# PS32_lite_rev_a_public.net
KiCad netlist of a schematic drawn in Altium Designer
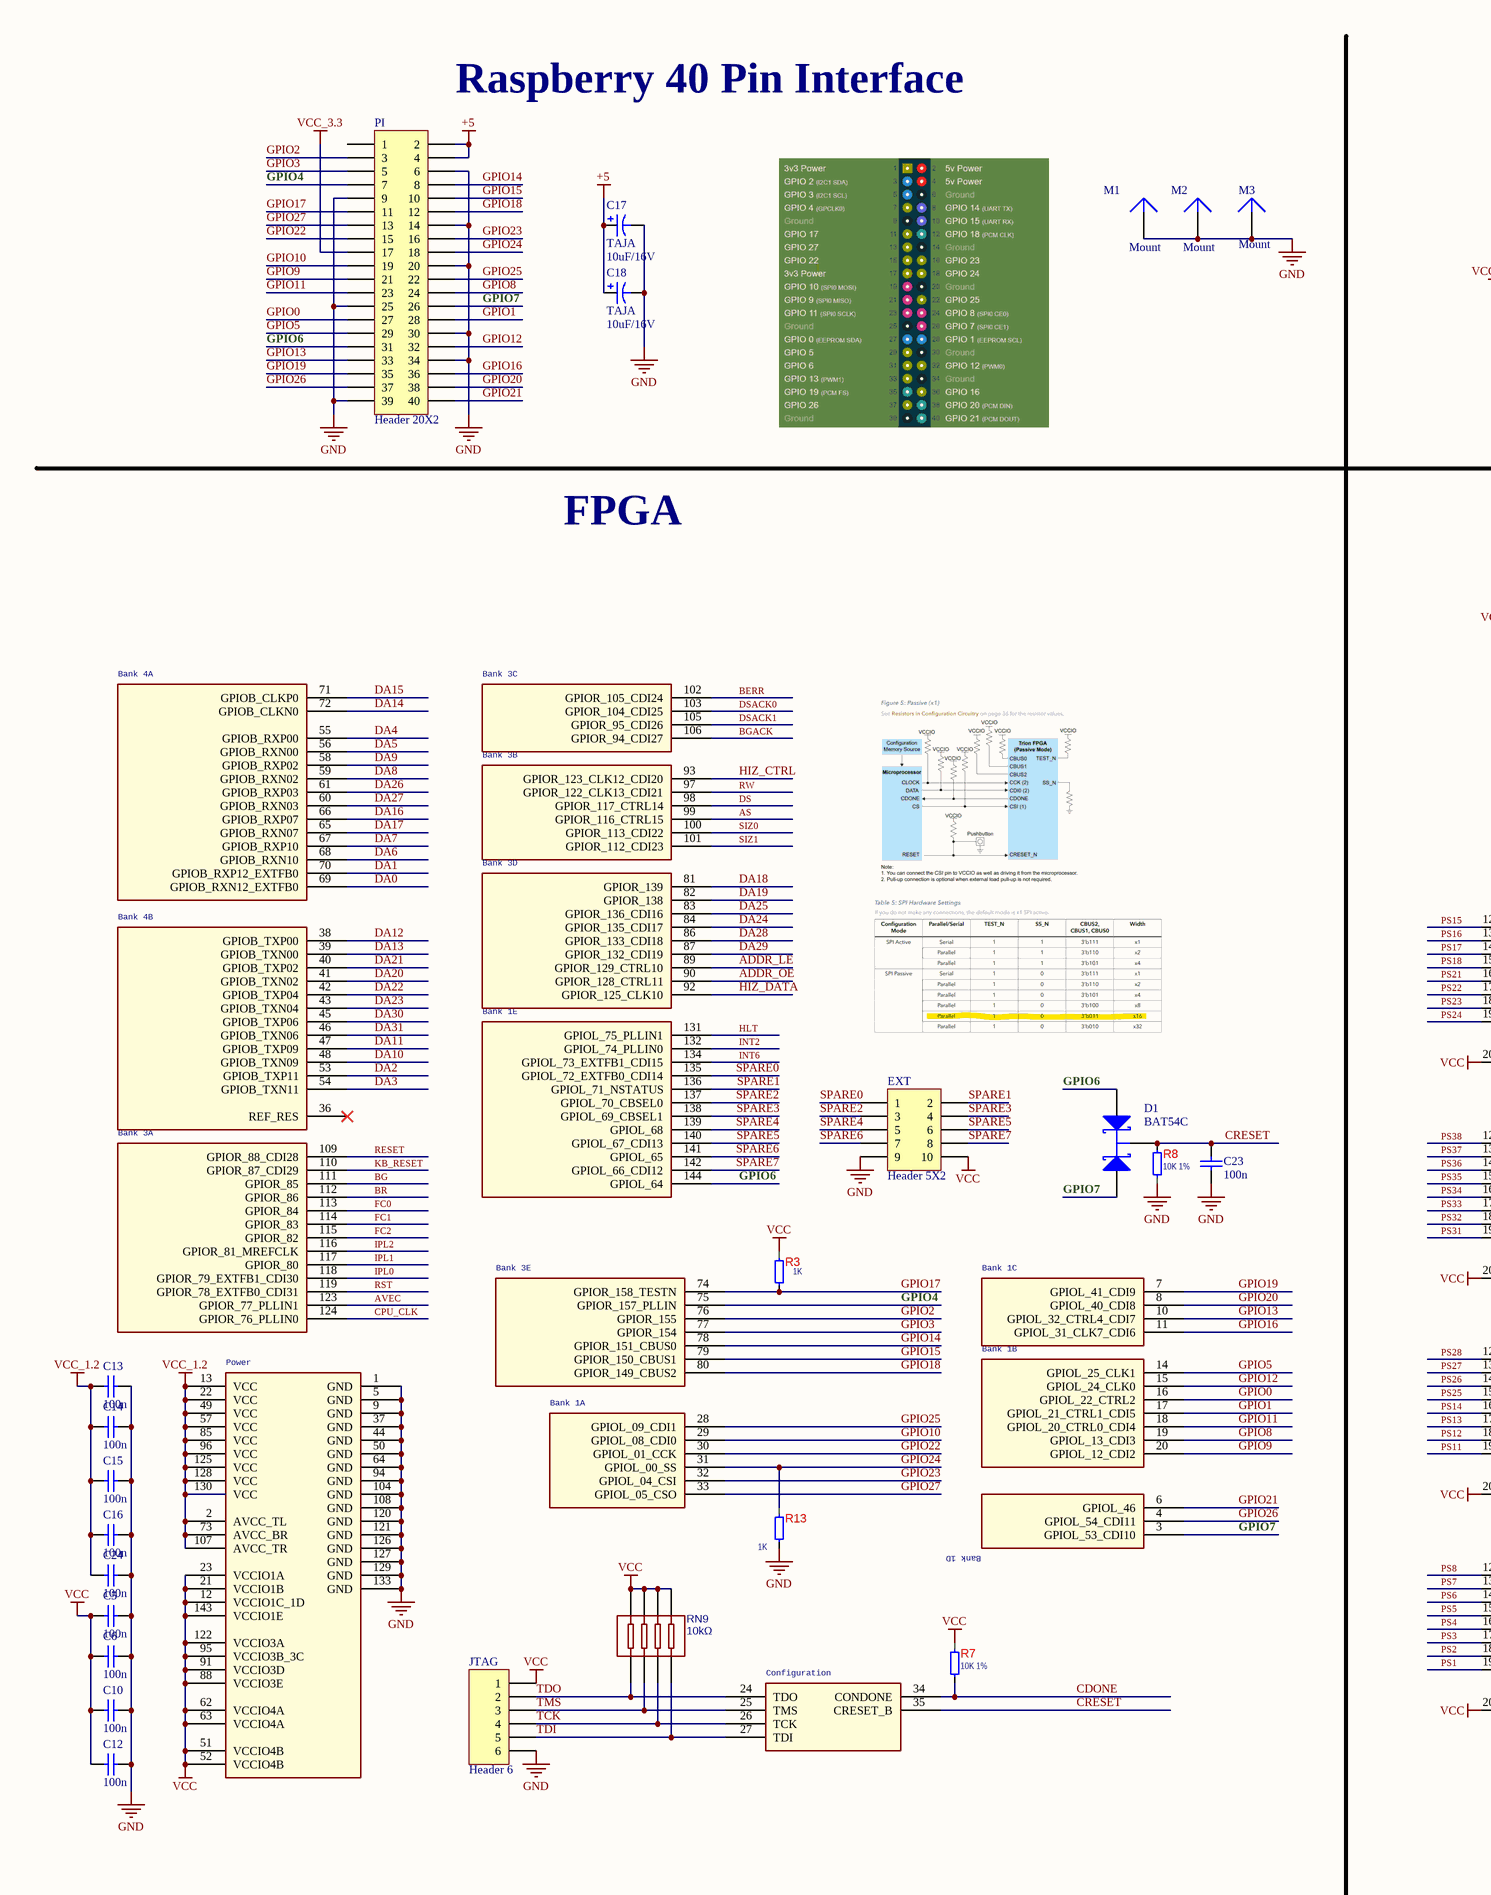
[diagram p0: PS32_lite_rev_a_public.SchDoc, left]
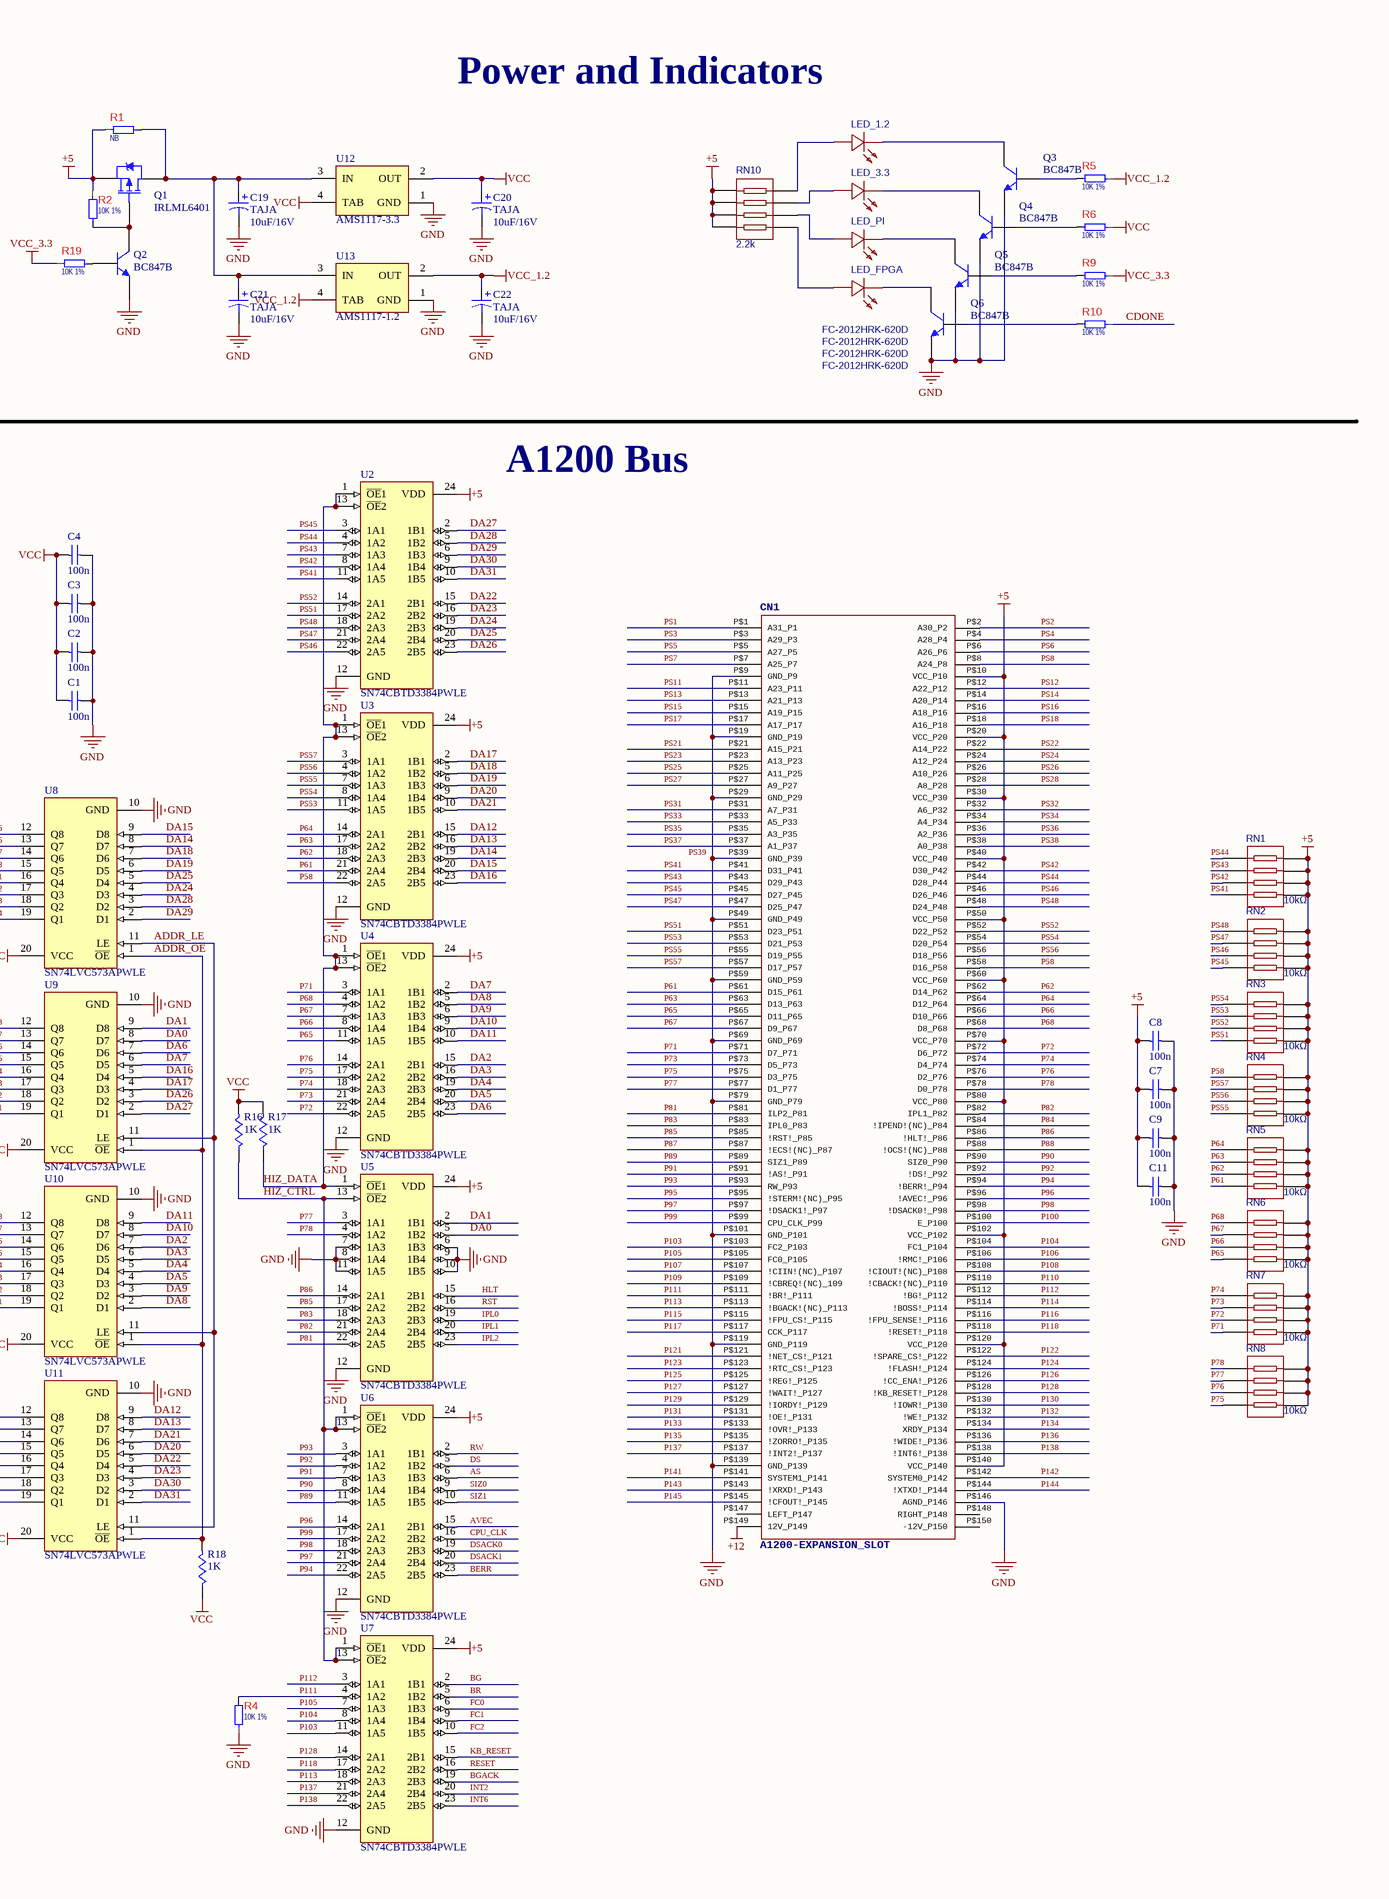
[diagram p1: PS32_lite_rev_a_public.SchDoc, right]

(export (version "E")
  (design (tool "Eeschema 10.0.6"))
  (components
    (comp (ref "C1")
      (value "100n")
      (footprint "1608[0603]")
      (description "Capacitor (Semiconductor SIM Model)")
      (fields (field (name "Comment") "Cap Semi") (field (name "PUBLISHER") "Altium Limited"))
      (libsource (lib "Miscellaneous Devices") (part "Cap Semi"))
    )
    (comp (ref "C2")
      (value "100n")
      (footprint "1608[0603]")
      (description "Capacitor (Semiconductor SIM Model)")
      (fields (field (name "Comment") "Cap Semi") (field (name "PUBLISHER") "Altium Limited"))
      (libsource (lib "Miscellaneous Devices") (part "Cap Semi"))
    )
    (comp (ref "C3")
      (value "100n")
      (footprint "1608[0603]")
      (description "Capacitor (Semiconductor SIM Model)")
      (fields (field (name "Comment") "Cap Semi") (field (name "PUBLISHER") "Altium Limited"))
      (libsource (lib "Miscellaneous Devices") (part "Cap Semi"))
    )
    (comp (ref "C4")
      (value "100n")
      (footprint "1608[0603]")
      (description "Capacitor (Semiconductor SIM Model)")
      (fields (field (name "Comment") "Cap Semi") (field (name "PUBLISHER") "Altium Limited"))
      (libsource (lib "Miscellaneous Devices") (part "Cap Semi"))
    )
    (comp (ref "C5")
      (value "100n")
      (footprint "1608[0603]")
      (description "Capacitor (Semiconductor SIM Model)")
      (fields (field (name "Comment") "Cap Semi") (field (name "PUBLISHER") "Altium Limited"))
      (libsource (lib "Miscellaneous Devices") (part "Cap Semi"))
    )
    (comp (ref "C6")
      (value "100n")
      (footprint "1608[0603]")
      (description "Capacitor (Semiconductor SIM Model)")
      (fields (field (name "Comment") "Cap Semi") (field (name "PUBLISHER") "Altium Limited"))
      (libsource (lib "Miscellaneous Devices") (part "Cap Semi"))
    )
    (comp (ref "C7")
      (value "100n")
      (footprint "1608[0603]")
      (description "Capacitor (Semiconductor SIM Model)")
      (fields (field (name "Comment") "Cap Semi") (field (name "PUBLISHER") "Altium Limited"))
      (libsource (lib "Miscellaneous Devices") (part "Cap Semi"))
    )
    (comp (ref "C8")
      (value "100n")
      (footprint "1608[0603]")
      (description "Capacitor (Semiconductor SIM Model)")
      (fields (field (name "Comment") "Cap Semi") (field (name "PUBLISHER") "Altium Limited"))
      (libsource (lib "Miscellaneous Devices") (part "Cap Semi"))
    )
    (comp (ref "C9")
      (value "100n")
      (footprint "1608[0603]")
      (description "Capacitor (Semiconductor SIM Model)")
      (fields (field (name "Comment") "Cap Semi") (field (name "PUBLISHER") "Altium Limited"))
      (libsource (lib "Miscellaneous Devices") (part "Cap Semi"))
    )
    (comp (ref "C10")
      (value "100n")
      (footprint "1608[0603]")
      (description "Capacitor (Semiconductor SIM Model)")
      (fields (field (name "Comment") "Cap Semi") (field (name "PUBLISHER") "Altium Limited"))
      (libsource (lib "Miscellaneous Devices") (part "Cap Semi"))
    )
    (comp (ref "C11")
      (value "100n")
      (footprint "1608[0603]")
      (description "Capacitor (Semiconductor SIM Model)")
      (fields (field (name "Comment") "Cap Semi") (field (name "PUBLISHER") "Altium Limited"))
      (libsource (lib "Miscellaneous Devices") (part "Cap Semi"))
    )
    (comp (ref "C12")
      (value "100n")
      (footprint "1608[0603]")
      (description "Capacitor (Semiconductor SIM Model)")
      (fields (field (name "Comment") "Cap Semi") (field (name "PUBLISHER") "Altium Limited"))
      (libsource (lib "Miscellaneous Devices") (part "Cap Semi"))
    )
    (comp (ref "C13")
      (value "100n")
      (footprint "1608[0603]")
      (description "Capacitor (Semiconductor SIM Model)")
      (fields (field (name "Comment") "Cap Semi") (field (name "PUBLISHER") "Altium Limited"))
      (libsource (lib "Miscellaneous Devices") (part "Cap Semi"))
    )
    (comp (ref "C14")
      (value "100n")
      (footprint "1608[0603]")
      (description "Capacitor (Semiconductor SIM Model)")
      (fields (field (name "Comment") "Cap Semi") (field (name "PUBLISHER") "Altium Limited"))
      (libsource (lib "Miscellaneous Devices") (part "Cap Semi"))
    )
    (comp (ref "C15")
      (value "100n")
      (footprint "1608[0603]")
      (description "Capacitor (Semiconductor SIM Model)")
      (fields (field (name "Comment") "Cap Semi") (field (name "PUBLISHER") "Altium Limited"))
      (libsource (lib "Miscellaneous Devices") (part "Cap Semi"))
    )
    (comp (ref "C16")
      (value "100n")
      (footprint "1608[0603]")
      (description "Capacitor (Semiconductor SIM Model)")
      (fields (field (name "Comment") "Cap Semi") (field (name "PUBLISHER") "Altium Limited"))
      (libsource (lib "Miscellaneous Devices") (part "Cap Semi"))
    )
    (comp (ref "C17")
      (value "TAJA")
      (footprint "T")
      (description "Solid Tantalum Chip Capacitor, Low Profile T491 Series - Industrial Grade")
      (fields (field (name "ALTIUM_VALUE") "10uF/16V") (field (name "PUBLISHER") "Altium Limited"))
      (libsource (lib "KEMET Chip Capacitor") (part "T491T"))
    )
    (comp (ref "C18")
      (value "TAJA")
      (footprint "T")
      (description "Solid Tantalum Chip Capacitor, Low Profile T491 Series - Industrial Grade")
      (fields (field (name "ALTIUM_VALUE") "10uF/16V") (field (name "PUBLISHER") "Altium Limited"))
      (libsource (lib "KEMET Chip Capacitor") (part "T491T"))
    )
    (comp (ref "C19")
      (value "TAJA")
      (footprint "T")
      (description "Solid Tantalum Chip Capacitor, Low Profile T491 Series - Industrial Grade")
      (fields (field (name "ALTIUM_VALUE") "10uF/16V") (field (name "PUBLISHER") "Altium Limited"))
      (libsource (lib "KEMET Chip Capacitor") (part "T491T"))
    )
    (comp (ref "C20")
      (value "TAJA")
      (footprint "T")
      (description "Solid Tantalum Chip Capacitor, Low Profile T491 Series - Industrial Grade")
      (fields (field (name "ALTIUM_VALUE") "10uF/16V") (field (name "PUBLISHER") "Altium Limited"))
      (libsource (lib "KEMET Chip Capacitor") (part "T491T"))
    )
    (comp (ref "C21")
      (value "TAJA")
      (footprint "T")
      (description "Solid Tantalum Chip Capacitor, Low Profile T491 Series - Industrial Grade")
      (fields (field (name "ALTIUM_VALUE") "10uF/16V") (field (name "PUBLISHER") "Altium Limited"))
      (libsource (lib "KEMET Chip Capacitor") (part "T491T"))
    )
    (comp (ref "C22")
      (value "TAJA")
      (footprint "T")
      (description "Solid Tantalum Chip Capacitor, Low Profile T491 Series - Industrial Grade")
      (fields (field (name "ALTIUM_VALUE") "10uF/16V") (field (name "PUBLISHER") "Altium Limited"))
      (libsource (lib "KEMET Chip Capacitor") (part "T491T"))
    )
    (comp (ref "C23")
      (value "100n")
      (footprint "1608[0603]")
      (description "Capacitor (Semiconductor SIM Model)")
      (fields (field (name "Comment") "Cap Semi") (field (name "PUBLISHER") "Altium Limited"))
      (libsource (lib "Miscellaneous Devices") (part "Cap Semi"))
    )
    (comp (ref "C24")
      (value "100n")
      (footprint "1608[0603]")
      (description "Capacitor (Semiconductor SIM Model)")
      (fields (field (name "Comment") "Cap Semi") (field (name "PUBLISHER") "Altium Limited"))
      (libsource (lib "Miscellaneous Devices") (part "Cap Semi"))
    )
    (comp (ref "CN1")
      (value "A1200-EXPANSION_SLOT")
      (footprint "CON_150")
      (libsource (lib "Amiga") (part "A1200-EXPANSION_SLOT-SMALL-HOLES"))
    )
    (comp (ref "D1")
      (value "BAT54C")
      (footprint "SOT23_N")
      (description "Schottky Barrier Double Diode")
      (fields (field (name "PUBLISHER") "Altium Limited"))
      (libsource (lib "Philips Discrete Diode - Schottky") (part "BAT54C"))
    )
    (comp (ref "EXT")
      (value "Header 5X2")
      (footprint "HDR2X5")
      (description "Header, 5-Pin, Dual row")
      (fields (field (name "PUBLISHER") "Altium Limited"))
      (libsource (lib "Miscellaneous Connectors") (part "Header 5X2"))
    )
    (comp (ref "JTAG")
      (value "Header 6")
      (footprint "HDR1X6")
      (description "Header, 6-Pin")
      (fields (field (name "PUBLISHER") "Altium Limited"))
      (libsource (lib "Miscellaneous Connectors") (part "Header 6"))
    )
    (comp (ref "LED_1.2")
      (value "FC-2012HRK-620D")
      (footprint "LED0805-RD")
      (fields (field (name "BOM_SUPPLIER PART") "C84256"))
      (libsource (lib "altium-import") (part "root_2_FC-2012HRK-620D_"))
    )
    (comp (ref "LED_3.3")
      (value "FC-2012HRK-620D")
      (footprint "LED0805-RD")
      (fields (field (name "BOM_SUPPLIER PART") "C84256"))
      (libsource (lib "altium-import") (part "root_2_FC-2012HRK-620D_"))
    )
    (comp (ref "LED_FPGA")
      (value "FC-2012HRK-620D")
      (footprint "LED0805-RD")
      (fields (field (name "BOM_SUPPLIER PART") "C84256"))
      (libsource (lib "altium-import") (part "root_2_FC-2012HRK-620D_"))
    )
    (comp (ref "LED_PI")
      (value "FC-2012HRK-620D")
      (footprint "LED0805-RD")
      (fields (field (name "BOM_SUPPLIER PART") "C84256"))
      (libsource (lib "altium-import") (part "root_2_FC-2012HRK-620D_"))
    )
    (comp (ref "M1")
      (value "Mount")
      (footprint "9774045151")
      (description "Plug")
      (fields (field (name "PUBLISHER") "Altium Limited"))
      (libsource (lib "Miscellaneous Connectors") (part "Plug"))
    )
    (comp (ref "M2")
      (value "Mount")
      (footprint "9774045151")
      (description "Plug")
      (fields (field (name "PUBLISHER") "Altium Limited"))
      (libsource (lib "Miscellaneous Connectors") (part "Plug"))
    )
    (comp (ref "M3")
      (value "Mount")
      (footprint "9774045151")
      (description "Plug")
      (fields (field (name "PUBLISHER") "Altium Limited"))
      (libsource (lib "Miscellaneous Connectors") (part "Plug"))
    )
    (comp (ref "PI")
      (value "Header 20X2")
      (footprint "CONN-SMD_FH-00369")
      (description "Header, 20-Pin, Dual row")
      (fields (field (name "PUBLISHER") "Altium Limited"))
      (libsource (lib "Miscellaneous Connectors") (part "Header 20X2"))
    )
    (comp (ref "Q1")
      (value "IRLML6401")
      (footprint "Micro3_N")
      (description "HEXFET Power MOSFET")
      (fields (field (name "PUBLISHER") "Altium Limited"))
      (libsource (lib "IR Discrete MOSFET - Power") (part "IRLML6401"))
    )
    (comp (ref "Q2")
      (value "BC847B")
      (footprint "SOT23_N")
      (description "NPN General-purpose Transistor")
      (fields (field (name "PUBLISHER") "Altium Limited"))
      (libsource (lib "Philips Discrete BJT - Low Power") (part "BC847B"))
    )
    (comp (ref "Q3")
      (value "BC847B")
      (footprint "SOT23_N")
      (description "NPN General-purpose Transistor")
      (fields (field (name "PUBLISHER") "Altium Limited"))
      (libsource (lib "Philips Discrete BJT - Low Power") (part "BC847B"))
    )
    (comp (ref "Q4")
      (value "BC847B")
      (footprint "SOT23_N")
      (description "NPN General-purpose Transistor")
      (fields (field (name "PUBLISHER") "Altium Limited"))
      (libsource (lib "Philips Discrete BJT - Low Power") (part "BC847B"))
    )
    (comp (ref "Q5")
      (value "BC847B")
      (footprint "SOT23_N")
      (description "NPN General-purpose Transistor")
      (fields (field (name "PUBLISHER") "Altium Limited"))
      (libsource (lib "Philips Discrete BJT - Low Power") (part "BC847B"))
    )
    (comp (ref "Q6")
      (value "BC847B")
      (footprint "SOT23_N")
      (description "NPN General-purpose Transistor")
      (fields (field (name "PUBLISHER") "Altium Limited"))
      (libsource (lib "Philips Discrete BJT - Low Power") (part "BC847B"))
    )
    (comp (ref "R1")
      (value "E0424-846-00")
      (footprint "1608[0603]")
      (description "Widerstand")
      (fields (field (name "BAUTEILTYP (ALTIUM)") "NB"))
      (libsource (lib "HKRSQL1") (part "R_STD"))
    )
    (comp (ref "R2")
      (value "E0424-846-00")
      (footprint "1608[0603]")
      (description "Widerstand")
      (fields (field (name "BAUTEILTYP (ALTIUM)") "10K 1%"))
      (libsource (lib "HKRSQL1") (part "R_STD"))
    )
    (comp (ref "R3")
      (value "E0424-846-00")
      (footprint "1608[0603]")
      (description "Widerstand")
      (fields (field (name "BAUTEILTYP (ALTIUM)") "1K"))
      (libsource (lib "HKRSQL1") (part "R_STD"))
    )
    (comp (ref "R4")
      (value "E0424-846-00")
      (footprint "1608[0603]")
      (description "Widerstand")
      (fields (field (name "BAUTEILTYP (ALTIUM)") "10K 1%"))
      (libsource (lib "HKRSQL1") (part "R_STD"))
    )
    (comp (ref "R5")
      (value "E0424-846-00")
      (footprint "1608[0603]")
      (description "Widerstand")
      (fields (field (name "BAUTEILTYP (ALTIUM)") "10K 1%"))
      (libsource (lib "HKRSQL1") (part "R_STD"))
    )
    (comp (ref "R6")
      (value "E0424-846-00")
      (footprint "1608[0603]")
      (description "Widerstand")
      (fields (field (name "BAUTEILTYP (ALTIUM)") "10K 1%"))
      (libsource (lib "HKRSQL1") (part "R_STD"))
    )
    (comp (ref "R7")
      (value "E0424-846-00")
      (footprint "1608[0603]")
      (description "Widerstand")
      (fields (field (name "BAUTEILTYP (ALTIUM)") "10K 1%"))
      (libsource (lib "HKRSQL1") (part "R_STD"))
    )
    (comp (ref "R8")
      (value "E0424-846-00")
      (footprint "1608[0603]")
      (description "Widerstand")
      (fields (field (name "BAUTEILTYP (ALTIUM)") "10K 1%"))
      (libsource (lib "HKRSQL1") (part "R_STD"))
    )
    (comp (ref "R9")
      (value "E0424-846-00")
      (footprint "1608[0603]")
      (description "Widerstand")
      (fields (field (name "BAUTEILTYP (ALTIUM)") "10K 1%"))
      (libsource (lib "HKRSQL1") (part "R_STD"))
    )
    (comp (ref "R10")
      (value "E0424-846-00")
      (footprint "1608[0603]")
      (description "Widerstand")
      (fields (field (name "BAUTEILTYP (ALTIUM)") "10K 1%"))
      (libsource (lib "HKRSQL1") (part "R_STD"))
    )
    (comp (ref "R13")
      (value "E0424-846-00")
      (footprint "1608[0603]")
      (description "Widerstand")
      (fields (field (name "BAUTEILTYP (ALTIUM)") "1K"))
      (libsource (lib "HKRSQL1") (part "R_STD"))
    )
    (comp (ref "R16")
      (value "1K")
      (footprint "1608[0603]")
      (description "RES 22 OHM 1/16W 5% 0402")
      (fields (field (name "PART NUMBER") "009-00020") (field (name "TOLERANCE") "0.05"))
      (libsource (lib "pcm") (part "004-00008"))
    )
    (comp (ref "R17")
      (value "1K")
      (footprint "1608[0603]")
      (description "RES 22 OHM 1/16W 5% 0402")
      (fields (field (name "PART NUMBER") "009-00020") (field (name "TOLERANCE") "0.05"))
      (libsource (lib "pcm") (part "004-00008"))
    )
    (comp (ref "R18")
      (value "1K")
      (footprint "1608[0603]")
      (description "RES 22 OHM 1/16W 5% 0402")
      (fields (field (name "PART NUMBER") "009-00020") (field (name "TOLERANCE") "0.05"))
      (libsource (lib "pcm") (part "004-00008"))
    )
    (comp (ref "R19")
      (value "E0424-846-00")
      (footprint "1608[0603]")
      (description "Widerstand")
      (fields (field (name "BAUTEILTYP (ALTIUM)") "10K 1%"))
      (libsource (lib "HKRSQL1") (part "R_STD"))
    )
    (comp (ref "RN1")
      (value "10kΩ")
      (footprint "RES-ARRAY-SMD_0603-8P-L3.2-W1.6-BL")
      (fields
        (field (name "BOM_MANUFACTURER PART") "4D03WGJ0103T5E")
        (field (name "BOM_SUPPLIER PART") "C29718")
      )
      (libsource (lib "altium-import") (part "root_0_mirrored_10kΩ_"))
    )
    (comp (ref "RN2")
      (value "10kΩ")
      (footprint "RES-ARRAY-SMD_0603-8P-L3.2-W1.6-BL")
      (fields
        (field (name "BOM_MANUFACTURER PART") "4D03WGJ0103T5E")
        (field (name "BOM_SUPPLIER PART") "C29718")
      )
      (libsource (lib "altium-import") (part "root_0_mirrored_10kΩ_"))
    )
    (comp (ref "RN3")
      (value "10kΩ")
      (footprint "RES-ARRAY-SMD_0603-8P-L3.2-W1.6-BL")
      (fields
        (field (name "BOM_MANUFACTURER PART") "4D03WGJ0103T5E")
        (field (name "BOM_SUPPLIER PART") "C29718")
      )
      (libsource (lib "altium-import") (part "root_0_mirrored_10kΩ_"))
    )
    (comp (ref "RN4")
      (value "10kΩ")
      (footprint "RES-ARRAY-SMD_0603-8P-L3.2-W1.6-BL")
      (fields
        (field (name "BOM_MANUFACTURER PART") "4D03WGJ0103T5E")
        (field (name "BOM_SUPPLIER PART") "C29718")
      )
      (libsource (lib "altium-import") (part "root_0_mirrored_10kΩ_"))
    )
    (comp (ref "RN5")
      (value "10kΩ")
      (footprint "RES-ARRAY-SMD_0603-8P-L3.2-W1.6-BL")
      (fields
        (field (name "BOM_MANUFACTURER PART") "4D03WGJ0103T5E")
        (field (name "BOM_SUPPLIER PART") "C29718")
      )
      (libsource (lib "altium-import") (part "root_0_mirrored_10kΩ_"))
    )
    (comp (ref "RN6")
      (value "10kΩ")
      (footprint "RES-ARRAY-SMD_0603-8P-L3.2-W1.6-BL")
      (fields
        (field (name "BOM_MANUFACTURER PART") "4D03WGJ0103T5E")
        (field (name "BOM_SUPPLIER PART") "C29718")
      )
      (libsource (lib "altium-import") (part "root_0_mirrored_10kΩ_"))
    )
    (comp (ref "RN7")
      (value "10kΩ")
      (footprint "RES-ARRAY-SMD_0603-8P-L3.2-W1.6-BL")
      (fields
        (field (name "BOM_MANUFACTURER PART") "4D03WGJ0103T5E")
        (field (name "BOM_SUPPLIER PART") "C29718")
      )
      (libsource (lib "altium-import") (part "root_0_mirrored_10kΩ_"))
    )
    (comp (ref "RN8")
      (value "10kΩ")
      (footprint "RES-ARRAY-SMD_0603-8P-L3.2-W1.6-BL")
      (fields
        (field (name "BOM_MANUFACTURER PART") "4D03WGJ0103T5E")
        (field (name "BOM_SUPPLIER PART") "C29718")
      )
      (libsource (lib "altium-import") (part "root_0_mirrored_10kΩ_"))
    )
    (comp (ref "RN9")
      (value "10kΩ")
      (footprint "RES-ARRAY-SMD_0603-8P-L3.2-W1.6-BL")
      (fields
        (field (name "BOM_MANUFACTURER PART") "4D03WGJ0103T5E")
        (field (name "BOM_SUPPLIER PART") "C29718")
      )
      (libsource (lib "altium-import") (part "root_3_mirrored_10kΩ_"))
    )
    (comp (ref "RN10")
      (value "2.2k")
      (footprint "RES-ARRAY-SMD_0603-8P-L3.2-W1.6-BL")
      (fields
        (field (name "BOM_MANUFACTURER PART") "4D03WGJ0103T5E")
        (field (name "BOM_SUPPLIER PART") "C29718")
      )
      (libsource (lib "altium-import") (part "root_2_mirrored_10kΩ_"))
    )
    (comp (ref "U1")
      (value "T8Q144Cx")
      (footprint "LQFP144")
      (libsource (lib "orcadt8-v1.3_Library") (part "T8Q144Cx"))
    )
    (comp (ref "U2")
      (value "SN74CBTD3384PWLE")
      (footprint "PW024_N")
      (description "10-Bit FET Bus Switch with Level Shifting")
      (fields (field (name "PUBLISHER") "Altium Limited"))
      (libsource (lib "TI Logic Switch") (part "SN74CBTD3384PWLE"))
    )
    (comp (ref "U3")
      (value "SN74CBTD3384PWLE")
      (footprint "PW024_N")
      (description "10-Bit FET Bus Switch with Level Shifting")
      (fields (field (name "PUBLISHER") "Altium Limited"))
      (libsource (lib "TI Logic Switch") (part "SN74CBTD3384PWLE"))
    )
    (comp (ref "U4")
      (value "SN74CBTD3384PWLE")
      (footprint "PW024_N")
      (description "10-Bit FET Bus Switch with Level Shifting")
      (fields (field (name "PUBLISHER") "Altium Limited"))
      (libsource (lib "TI Logic Switch") (part "SN74CBTD3384PWLE"))
    )
    (comp (ref "U5")
      (value "SN74CBTD3384PWLE")
      (footprint "PW024_N")
      (description "10-Bit FET Bus Switch with Level Shifting")
      (fields (field (name "PUBLISHER") "Altium Limited"))
      (libsource (lib "TI Logic Switch") (part "SN74CBTD3384PWLE"))
    )
    (comp (ref "U6")
      (value "SN74CBTD3384PWLE")
      (footprint "PW024_N")
      (description "10-Bit FET Bus Switch with Level Shifting")
      (fields (field (name "PUBLISHER") "Altium Limited"))
      (libsource (lib "TI Logic Switch") (part "SN74CBTD3384PWLE"))
    )
    (comp (ref "U7")
      (value "SN74CBTD3384PWLE")
      (footprint "PW024_N")
      (description "10-Bit FET Bus Switch with Level Shifting")
      (fields (field (name "PUBLISHER") "Altium Limited"))
      (libsource (lib "TI Logic Switch") (part "SN74CBTD3384PWLE"))
    )
    (comp (ref "U8")
      (value "SN74LVC573APWLE")
      (footprint "PW020")
      (description "Octal Transparent D-Type Latch with 3-State Outputs")
      (fields (field (name "PUBLISHER") "Altium Limited"))
      (libsource (lib "TI Logic Latch") (part "SN74LVC573APWLE"))
    )
    (comp (ref "U9")
      (value "SN74LVC573APWLE")
      (footprint "PW020")
      (description "Octal Transparent D-Type Latch with 3-State Outputs")
      (fields (field (name "PUBLISHER") "Altium Limited"))
      (libsource (lib "TI Logic Latch") (part "SN74LVC573APWLE"))
    )
    (comp (ref "U10")
      (value "SN74LVC573APWLE")
      (footprint "PW020")
      (description "Octal Transparent D-Type Latch with 3-State Outputs")
      (fields (field (name "PUBLISHER") "Altium Limited"))
      (libsource (lib "TI Logic Latch") (part "SN74LVC573APWLE"))
    )
    (comp (ref "U11")
      (value "SN74LVC573APWLE")
      (footprint "PW020")
      (description "Octal Transparent D-Type Latch with 3-State Outputs")
      (fields (field (name "PUBLISHER") "Altium Limited"))
      (libsource (lib "TI Logic Latch") (part "SN74LVC573APWLE"))
    )
    (comp (ref "U12")
      (value "AMS1117-3.3")
      (footprint "MP04A_N")
      (description "800mA Low-Dropout Linear Regulator, 4-pin SOT-223")
      (fields
        (field (name "PARTNUMBER") "LM1117IMPX-3.3")
        (field (name "MANUFACTURER") "National Semiconductor")
        (field (name "PUBLISHER") "Altium Limited")
      )
      (libsource (lib "NSC LDO") (part "LM1117IMPX-3.3"))
    )
    (comp (ref "U13")
      (value "AMS1117-1.2")
      (footprint "MP04A_N")
      (description "800mA Low-Dropout Linear Regulator, 4-pin SOT-223")
      (fields
        (field (name "PARTNUMBER") "LM1117IMPX-3.3")
        (field (name "MANUFACTURER") "National Semiconductor")
        (field (name "PUBLISHER") "Altium Limited")
      )
      (libsource (lib "NSC LDO") (part "LM1117IMPX-3.3"))
    )
  )
  (nets
    (net (code "1") (name "+5") (class "Default")
      (node (ref "C11") (pin "2") (pinfunction "2_2") (pintype "passive"))
      (node (ref "C17") (pin "1") (pinfunction "1_1") (pintype "passive"))
      (node (ref "C18") (pin "1") (pinfunction "1_1") (pintype "passive"))
      (node (ref "C7") (pin "2") (pinfunction "2_2") (pintype "passive"))
      (node (ref "C8") (pin "2") (pinfunction "2_2") (pintype "passive"))
      (node (ref "C9") (pin "2") (pinfunction "2_2") (pintype "passive"))
      (node (ref "CN1") (pin "P$10") (pinfunction "VCC_P10_P$10") (pintype "passive"))
      (node (ref "CN1") (pin "P$102") (pinfunction "VCC_P102_P$102") (pintype "passive"))
      (node (ref "CN1") (pin "P$120") (pinfunction "VCC_P120_P$120") (pintype "passive"))
      (node (ref "CN1") (pin "P$140") (pinfunction "VCC_P140_P$140") (pintype "passive"))
      (node (ref "CN1") (pin "P$20") (pinfunction "VCC_P20_P$20") (pintype "passive"))
      (node (ref "CN1") (pin "P$30") (pinfunction "VCC_P30_P$30") (pintype "passive"))
      (node (ref "CN1") (pin "P$40") (pinfunction "VCC_P40_P$40") (pintype "passive"))
      (node (ref "CN1") (pin "P$50") (pinfunction "VCC_P50_P$50") (pintype "passive"))
      (node (ref "CN1") (pin "P$60") (pinfunction "VCC_P60_P$60") (pintype "passive"))
      (node (ref "CN1") (pin "P$70") (pinfunction "VCC_P70_P$70") (pintype "passive"))
      (node (ref "CN1") (pin "P$80") (pinfunction "VCC_P80_P$80") (pintype "passive"))
      (node (ref "PI") (pin "2") (pinfunction "2_2") (pintype "passive"))
      (node (ref "PI") (pin "4") (pinfunction "4_4") (pintype "passive"))
      (node (ref "Q1") (pin "2") (pinfunction "S_2") (pintype "passive"))
      (node (ref "R1") (pin "2") (pintype "passive"))
      (node (ref "R2") (pin "2") (pintype "passive"))
      (node (ref "RN1") (pin "1") (pinfunction "1_1") (pintype "passive"))
      (node (ref "RN1") (pin "2") (pinfunction "2_2") (pintype "passive"))
      (node (ref "RN1") (pin "3") (pinfunction "3_3") (pintype "passive"))
      (node (ref "RN1") (pin "4") (pinfunction "4_4") (pintype "passive"))
      (node (ref "RN10") (pin "1") (pinfunction "1_1") (pintype "passive"))
      (node (ref "RN10") (pin "2") (pinfunction "2_2") (pintype "passive"))
      (node (ref "RN10") (pin "3") (pinfunction "3_3") (pintype "passive"))
      (node (ref "RN10") (pin "4") (pinfunction "4_4") (pintype "passive"))
      (node (ref "RN2") (pin "1") (pinfunction "1_1") (pintype "passive"))
      (node (ref "RN2") (pin "2") (pinfunction "2_2") (pintype "passive"))
      (node (ref "RN2") (pin "3") (pinfunction "3_3") (pintype "passive"))
      (node (ref "RN2") (pin "4") (pinfunction "4_4") (pintype "passive"))
      (node (ref "RN3") (pin "1") (pinfunction "1_1") (pintype "passive"))
      (node (ref "RN3") (pin "2") (pinfunction "2_2") (pintype "passive"))
      (node (ref "RN3") (pin "3") (pinfunction "3_3") (pintype "passive"))
      (node (ref "RN3") (pin "4") (pinfunction "4_4") (pintype "passive"))
      (node (ref "RN4") (pin "1") (pinfunction "1_1") (pintype "passive"))
      (node (ref "RN4") (pin "2") (pinfunction "2_2") (pintype "passive"))
      (node (ref "RN4") (pin "3") (pinfunction "3_3") (pintype "passive"))
      (node (ref "RN4") (pin "4") (pinfunction "4_4") (pintype "passive"))
      (node (ref "RN5") (pin "1") (pinfunction "1_1") (pintype "passive"))
      (node (ref "RN5") (pin "2") (pinfunction "2_2") (pintype "passive"))
      (node (ref "RN5") (pin "3") (pinfunction "3_3") (pintype "passive"))
      (node (ref "RN5") (pin "4") (pinfunction "4_4") (pintype "passive"))
      (node (ref "RN6") (pin "1") (pinfunction "1_1") (pintype "passive"))
      (node (ref "RN6") (pin "2") (pinfunction "2_2") (pintype "passive"))
      (node (ref "RN6") (pin "3") (pinfunction "3_3") (pintype "passive"))
      (node (ref "RN6") (pin "4") (pinfunction "4_4") (pintype "passive"))
      (node (ref "RN7") (pin "1") (pinfunction "1_1") (pintype "passive"))
      (node (ref "RN7") (pin "2") (pinfunction "2_2") (pintype "passive"))
      (node (ref "RN7") (pin "3") (pinfunction "3_3") (pintype "passive"))
      (node (ref "RN7") (pin "4") (pinfunction "4_4") (pintype "passive"))
      (node (ref "RN8") (pin "1") (pinfunction "1_1") (pintype "passive"))
      (node (ref "RN8") (pin "2") (pinfunction "2_2") (pintype "passive"))
      (node (ref "RN8") (pin "3") (pinfunction "3_3") (pintype "passive"))
      (node (ref "RN8") (pin "4") (pinfunction "4_4") (pintype "passive"))
      (node (ref "U2") (pin "24") (pinfunction "VDD_24") (pintype "power_in"))
      (node (ref "U3") (pin "24") (pinfunction "VDD_24") (pintype "power_in"))
      (node (ref "U4") (pin "24") (pinfunction "VDD_24") (pintype "power_in"))
      (node (ref "U5") (pin "24") (pinfunction "VDD_24") (pintype "power_in"))
      (node (ref "U6") (pin "24") (pinfunction "VDD_24") (pintype "power_in"))
      (node (ref "U7") (pin "24") (pinfunction "VDD_24") (pintype "power_in"))
    )
    (net (code "2") (name "+12") (class "Default")
      (node (ref "CN1") (pin "P$149") (pinfunction "12V_P149_P$149") (pintype "passive"))
    )
    (net (code "3") (name "/ADDR_LE") (class "Default")
      (node (ref "U1") (pin "89") (pinfunction "GPIOR_129_CTRL10_89") (pintype "passive"))
      (node (ref "U10") (pin "11") (pinfunction "LE_11") (pintype "input"))
      (node (ref "U11") (pin "11") (pinfunction "LE_11") (pintype "input"))
      (node (ref "U8") (pin "11") (pinfunction "LE_11") (pintype "input"))
      (node (ref "U9") (pin "11") (pinfunction "LE_11") (pintype "input"))
    )
    (net (code "4") (name "/ADDR_OE") (class "Default")
      (node (ref "R18") (pin "1") (pinfunction "1_1") (pintype "passive"))
      (node (ref "U1") (pin "90") (pinfunction "GPIOR_128_CTRL11_90") (pintype "passive"))
      (node (ref "U10") (pin "1") (pinfunction "~{OE}_1") (pintype "input"))
      (node (ref "U11") (pin "1") (pinfunction "~{OE}_1") (pintype "input"))
      (node (ref "U8") (pin "1") (pinfunction "~{OE}_1") (pintype "input"))
      (node (ref "U9") (pin "1") (pinfunction "~{OE}_1") (pintype "input"))
    )
    (net (code "5") (name "/AS") (class "Default")
      (node (ref "U1") (pin "99") (pinfunction "GPIOR_116_CTRL15_99") (pintype "passive"))
      (node (ref "U6") (pin "6") (pinfunction "1B3_6") (pintype "bidirectional"))
    )
    (net (code "6") (name "/AVEC") (class "Default")
      (node (ref "U1") (pin "123") (pinfunction "GPIOR_77_PLLIN1_123") (pintype "passive"))
      (node (ref "U6") (pin "15") (pinfunction "2B1_15") (pintype "bidirectional"))
    )
    (net (code "7") (name "/BERR") (class "Default")
      (node (ref "U1") (pin "102") (pinfunction "GPIOR_105_CDI24_102") (pintype "passive"))
      (node (ref "U6") (pin "23") (pinfunction "2B5_23") (pintype "bidirectional"))
    )
    (net (code "8") (name "/BG") (class "Default")
      (node (ref "U1") (pin "111") (pinfunction "GPIOR_85_111") (pintype "passive"))
      (node (ref "U7") (pin "2") (pinfunction "1B1_2") (pintype "bidirectional"))
    )
    (net (code "9") (name "/BGACK") (class "Default")
      (node (ref "U1") (pin "106") (pinfunction "GPIOR_94_CDI27_106") (pintype "passive"))
      (node (ref "U7") (pin "19") (pinfunction "2B3_19") (pintype "bidirectional"))
    )
    (net (code "10") (name "/BR") (class "Default")
      (node (ref "U1") (pin "112") (pinfunction "GPIOR_86_112") (pintype "passive"))
      (node (ref "U7") (pin "5") (pinfunction "1B2_5") (pintype "bidirectional"))
    )
    (net (code "11") (name "/CDONE") (class "Default")
      (node (ref "R10") (pin "2") (pintype "passive"))
      (node (ref "R7") (pin "1") (pintype "passive"))
      (node (ref "U1") (pin "34") (pinfunction "CONDONE_34") (pintype "passive"))
    )
    (net (code "12") (name "/CPU_CLK") (class "Default")
      (node (ref "U1") (pin "124") (pinfunction "GPIOR_76_PLLIN0_124") (pintype "passive"))
      (node (ref "U6") (pin "16") (pinfunction "2B2_16") (pintype "bidirectional"))
    )
    (net (code "13") (name "/CRESET") (class "Default")
      (node (ref "C23") (pin "1") (pinfunction "1_1") (pintype "passive"))
      (node (ref "D1") (pin "3") (pinfunction "K_3") (pintype "passive"))
      (node (ref "R8") (pin "1") (pintype "passive"))
      (node (ref "U1") (pin "35") (pinfunction "CRESET_B_35") (pintype "passive"))
    )
    (net (code "14") (name "/DA0") (class "Default")
      (node (ref "U1") (pin "69") (pinfunction "GPIOB_RXN12_EXTFB0_69") (pintype "passive"))
      (node (ref "U5") (pin "5") (pinfunction "1B2_5") (pintype "bidirectional"))
      (node (ref "U9") (pin "8") (pinfunction "D7_8") (pintype "input"))
    )
    (net (code "15") (name "/DA1") (class "Default")
      (node (ref "U1") (pin "70") (pinfunction "GPIOB_RXP12_EXTFB0_70") (pintype "passive"))
      (node (ref "U5") (pin "2") (pinfunction "1B1_2") (pintype "bidirectional"))
      (node (ref "U9") (pin "9") (pinfunction "D8_9") (pintype "input"))
    )
    (net (code "16") (name "/DA2") (class "Default")
      (node (ref "U1") (pin "53") (pinfunction "GPIOB_TXP11_53") (pintype "passive"))
      (node (ref "U10") (pin "7") (pinfunction "D6_7") (pintype "input"))
      (node (ref "U4") (pin "15") (pinfunction "2B1_15") (pintype "bidirectional"))
    )
    (net (code "17") (name "/DA3") (class "Default")
      (node (ref "U1") (pin "54") (pinfunction "GPIOB_TXN11_54") (pintype "passive"))
      (node (ref "U10") (pin "6") (pinfunction "D5_6") (pintype "input"))
      (node (ref "U4") (pin "16") (pinfunction "2B2_16") (pintype "bidirectional"))
    )
    (net (code "18") (name "/DA4") (class "Default")
      (node (ref "U1") (pin "55") (pinfunction "GPIOB_RXP00_55") (pintype "passive"))
      (node (ref "U10") (pin "5") (pinfunction "D4_5") (pintype "input"))
      (node (ref "U4") (pin "19") (pinfunction "2B3_19") (pintype "bidirectional"))
    )
    (net (code "19") (name "/DA5") (class "Default")
      (node (ref "U1") (pin "56") (pinfunction "GPIOB_RXN00_56") (pintype "passive"))
      (node (ref "U10") (pin "4") (pinfunction "D3_4") (pintype "input"))
      (node (ref "U4") (pin "20") (pinfunction "2B4_20") (pintype "bidirectional"))
    )
    (net (code "20") (name "/DA6") (class "Default")
      (node (ref "U1") (pin "68") (pinfunction "GPIOB_RXN10_68") (pintype "passive"))
      (node (ref "U4") (pin "23") (pinfunction "2B5_23") (pintype "bidirectional"))
      (node (ref "U9") (pin "7") (pinfunction "D6_7") (pintype "input"))
    )
    (net (code "21") (name "/DA7") (class "Default")
      (node (ref "U1") (pin "67") (pinfunction "GPIOB_RXP10_67") (pintype "passive"))
      (node (ref "U4") (pin "2") (pinfunction "1B1_2") (pintype "bidirectional"))
      (node (ref "U9") (pin "6") (pinfunction "D5_6") (pintype "input"))
    )
    (net (code "22") (name "/DA8") (class "Default")
      (node (ref "U1") (pin "59") (pinfunction "GPIOB_RXN02_59") (pintype "passive"))
      (node (ref "U10") (pin "2") (pinfunction "D1_2") (pintype "input"))
      (node (ref "U4") (pin "5") (pinfunction "1B2_5") (pintype "bidirectional"))
    )
    (net (code "23") (name "/DA9") (class "Default")
      (node (ref "U1") (pin "58") (pinfunction "GPIOB_RXP02_58") (pintype "passive"))
      (node (ref "U10") (pin "3") (pinfunction "D2_3") (pintype "input"))
      (node (ref "U4") (pin "6") (pinfunction "1B3_6") (pintype "bidirectional"))
    )
    (net (code "24") (name "/DA10") (class "Default")
      (node (ref "U1") (pin "48") (pinfunction "GPIOB_TXN09_48") (pintype "passive"))
      (node (ref "U10") (pin "8") (pinfunction "D7_8") (pintype "input"))
      (node (ref "U4") (pin "9") (pinfunction "1B4_9") (pintype "bidirectional"))
    )
    (net (code "25") (name "/DA11") (class "Default")
      (node (ref "U1") (pin "47") (pinfunction "GPIOB_TXP09_47") (pintype "passive"))
      (node (ref "U10") (pin "9") (pinfunction "D8_9") (pintype "input"))
      (node (ref "U4") (pin "10") (pinfunction "1B5_10") (pintype "bidirectional"))
    )
    (net (code "26") (name "/DA12") (class "Default")
      (node (ref "U1") (pin "38") (pinfunction "GPIOB_TXP00_38") (pintype "passive"))
      (node (ref "U11") (pin "9") (pinfunction "D8_9") (pintype "input"))
      (node (ref "U3") (pin "15") (pinfunction "2B1_15") (pintype "bidirectional"))
    )
    (net (code "27") (name "/DA13") (class "Default")
      (node (ref "U1") (pin "39") (pinfunction "GPIOB_TXN00_39") (pintype "passive"))
      (node (ref "U11") (pin "8") (pinfunction "D7_8") (pintype "input"))
      (node (ref "U3") (pin "16") (pinfunction "2B2_16") (pintype "bidirectional"))
    )
    (net (code "28") (name "/DA14") (class "Default")
      (node (ref "U1") (pin "72") (pinfunction "GPIOB_CLKN0_72") (pintype "passive"))
      (node (ref "U3") (pin "19") (pinfunction "2B3_19") (pintype "bidirectional"))
      (node (ref "U8") (pin "8") (pinfunction "D7_8") (pintype "input"))
    )
    (net (code "29") (name "/DA15") (class "Default")
      (node (ref "U1") (pin "71") (pinfunction "GPIOB_CLKP0_71") (pintype "passive"))
      (node (ref "U3") (pin "20") (pinfunction "2B4_20") (pintype "bidirectional"))
      (node (ref "U8") (pin "9") (pinfunction "D8_9") (pintype "input"))
    )
    (net (code "30") (name "/DA16") (class "Default")
      (node (ref "U1") (pin "66") (pinfunction "GPIOB_RXP07_66") (pintype "passive"))
      (node (ref "U3") (pin "23") (pinfunction "2B5_23") (pintype "bidirectional"))
      (node (ref "U9") (pin "5") (pinfunction "D4_5") (pintype "input"))
    )
    (net (code "31") (name "/DA17") (class "Default")
      (node (ref "U1") (pin "65") (pinfunction "GPIOB_RXN07_65") (pintype "passive"))
      (node (ref "U3") (pin "2") (pinfunction "1B1_2") (pintype "bidirectional"))
      (node (ref "U9") (pin "4") (pinfunction "D3_4") (pintype "input"))
    )
    (net (code "32") (name "/DA18") (class "Default")
      (node (ref "U1") (pin "81") (pinfunction "GPIOR_139_81") (pintype "passive"))
      (node (ref "U3") (pin "5") (pinfunction "1B2_5") (pintype "bidirectional"))
      (node (ref "U8") (pin "7") (pinfunction "D6_7") (pintype "input"))
    )
    (net (code "33") (name "/DA19") (class "Default")
      (node (ref "U1") (pin "82") (pinfunction "GPIOR_138_82") (pintype "passive"))
      (node (ref "U3") (pin "6") (pinfunction "1B3_6") (pintype "bidirectional"))
      (node (ref "U8") (pin "6") (pinfunction "D5_6") (pintype "input"))
    )
    (net (code "34") (name "/DA20") (class "Default")
      (node (ref "U1") (pin "41") (pinfunction "GPIOB_TXN02_41") (pintype "passive"))
      (node (ref "U11") (pin "6") (pinfunction "D5_6") (pintype "input"))
      (node (ref "U3") (pin "9") (pinfunction "1B4_9") (pintype "bidirectional"))
    )
    (net (code "35") (name "/DA21") (class "Default")
      (node (ref "U1") (pin "40") (pinfunction "GPIOB_TXP02_40") (pintype "passive"))
      (node (ref "U11") (pin "7") (pinfunction "D6_7") (pintype "input"))
      (node (ref "U3") (pin "10") (pinfunction "1B5_10") (pintype "bidirectional"))
    )
    (net (code "36") (name "/DA22") (class "Default")
      (node (ref "U1") (pin "42") (pinfunction "GPIOB_TXP04_42") (pintype "passive"))
      (node (ref "U11") (pin "5") (pinfunction "D4_5") (pintype "input"))
      (node (ref "U2") (pin "15") (pinfunction "2B1_15") (pintype "bidirectional"))
    )
    (net (code "37") (name "/DA23") (class "Default")
      (node (ref "U1") (pin "43") (pinfunction "GPIOB_TXN04_43") (pintype "passive"))
      (node (ref "U11") (pin "4") (pinfunction "D3_4") (pintype "input"))
      (node (ref "U2") (pin "16") (pinfunction "2B2_16") (pintype "bidirectional"))
    )
    (net (code "38") (name "/DA24") (class "Default")
      (node (ref "U1") (pin "84") (pinfunction "GPIOR_135_CDI17_84") (pintype "passive"))
      (node (ref "U2") (pin "19") (pinfunction "2B3_19") (pintype "bidirectional"))
      (node (ref "U8") (pin "4") (pinfunction "D3_4") (pintype "input"))
    )
    (net (code "39") (name "/DA25") (class "Default")
      (node (ref "U1") (pin "83") (pinfunction "GPIOR_136_CDI16_83") (pintype "passive"))
      (node (ref "U2") (pin "20") (pinfunction "2B4_20") (pintype "bidirectional"))
      (node (ref "U8") (pin "5") (pinfunction "D4_5") (pintype "input"))
    )
    (net (code "40") (name "/DA26") (class "Default")
      (node (ref "U1") (pin "61") (pinfunction "GPIOB_RXP03_61") (pintype "passive"))
      (node (ref "U2") (pin "23") (pinfunction "2B5_23") (pintype "bidirectional"))
      (node (ref "U9") (pin "3") (pinfunction "D2_3") (pintype "input"))
    )
    (net (code "41") (name "/DA27") (class "Default")
      (node (ref "U1") (pin "60") (pinfunction "GPIOB_RXN03_60") (pintype "passive"))
      (node (ref "U2") (pin "2") (pinfunction "1B1_2") (pintype "bidirectional"))
      (node (ref "U9") (pin "2") (pinfunction "D1_2") (pintype "input"))
    )
    (net (code "42") (name "/DA28") (class "Default")
      (node (ref "U1") (pin "86") (pinfunction "GPIOR_133_CDI18_86") (pintype "passive"))
      (node (ref "U2") (pin "5") (pinfunction "1B2_5") (pintype "bidirectional"))
      (node (ref "U8") (pin "3") (pinfunction "D2_3") (pintype "input"))
    )
    (net (code "43") (name "/DA29") (class "Default")
      (node (ref "U1") (pin "87") (pinfunction "GPIOR_132_CDI19_87") (pintype "passive"))
      (node (ref "U2") (pin "6") (pinfunction "1B3_6") (pintype "bidirectional"))
      (node (ref "U8") (pin "2") (pinfunction "D1_2") (pintype "input"))
    )
    (net (code "44") (name "/DA30") (class "Default")
      (node (ref "U1") (pin "45") (pinfunction "GPIOB_TXP06_45") (pintype "passive"))
      (node (ref "U11") (pin "3") (pinfunction "D2_3") (pintype "input"))
      (node (ref "U2") (pin "9") (pinfunction "1B4_9") (pintype "bidirectional"))
    )
    (net (code "45") (name "/DA31") (class "Default")
      (node (ref "U1") (pin "46") (pinfunction "GPIOB_TXN06_46") (pintype "passive"))
      (node (ref "U11") (pin "2") (pinfunction "D1_2") (pintype "input"))
      (node (ref "U2") (pin "10") (pinfunction "1B5_10") (pintype "bidirectional"))
    )
    (net (code "46") (name "/DS") (class "Default")
      (node (ref "U1") (pin "98") (pinfunction "GPIOR_117_CTRL14_98") (pintype "passive"))
      (node (ref "U6") (pin "5") (pinfunction "1B2_5") (pintype "bidirectional"))
    )
    (net (code "47") (name "/DSACK0") (class "Default")
      (node (ref "U1") (pin "103") (pinfunction "GPIOR_104_CDI25_103") (pintype "passive"))
      (node (ref "U6") (pin "19") (pinfunction "2B3_19") (pintype "bidirectional"))
    )
    (net (code "48") (name "/DSACK1") (class "Default")
      (node (ref "U1") (pin "105") (pinfunction "GPIOR_95_CDI26_105") (pintype "passive"))
      (node (ref "U6") (pin "20") (pinfunction "2B4_20") (pintype "bidirectional"))
    )
    (net (code "49") (name "/FC0") (class "Default")
      (node (ref "U1") (pin "113") (pinfunction "GPIOR_84_113") (pintype "passive"))
      (node (ref "U7") (pin "6") (pinfunction "1B3_6") (pintype "bidirectional"))
    )
    (net (code "50") (name "/FC1") (class "Default")
      (node (ref "U1") (pin "114") (pinfunction "GPIOR_83_114") (pintype "passive"))
      (node (ref "U7") (pin "9") (pinfunction "1B4_9") (pintype "bidirectional"))
    )
    (net (code "51") (name "/FC2") (class "Default")
      (node (ref "U1") (pin "115") (pinfunction "GPIOR_82_115") (pintype "passive"))
      (node (ref "U7") (pin "10") (pinfunction "1B5_10") (pintype "bidirectional"))
    )
    (net (code "52") (name "/GPIO0") (class "Default")
      (node (ref "PI") (pin "27") (pinfunction "27_27") (pintype "passive"))
      (node (ref "U1") (pin "16") (pinfunction "GPIOL_22_CTRL2_16") (pintype "passive"))
    )
    (net (code "53") (name "/GPIO1") (class "Default")
      (node (ref "PI") (pin "28") (pinfunction "28_28") (pintype "passive"))
      (node (ref "U1") (pin "17") (pinfunction "GPIOL_21_CTRL1_CDI5_17") (pintype "passive"))
    )
    (net (code "54") (name "/GPIO2") (class "Default")
      (node (ref "PI") (pin "3") (pinfunction "3_3") (pintype "passive"))
      (node (ref "U1") (pin "76") (pinfunction "GPIOR_155_76") (pintype "passive"))
    )
    (net (code "55") (name "/GPIO3") (class "Default")
      (node (ref "PI") (pin "5") (pinfunction "5_5") (pintype "passive"))
      (node (ref "U1") (pin "77") (pinfunction "GPIOR_154_77") (pintype "passive"))
    )
    (net (code "56") (name "/GPIO4") (class "Default")
      (node (ref "PI") (pin "7") (pinfunction "7_7") (pintype "passive"))
      (node (ref "U1") (pin "75") (pinfunction "GPIOR_157_PLLIN_75") (pintype "passive"))
    )
    (net (code "57") (name "/GPIO5") (class "Default")
      (node (ref "PI") (pin "29") (pinfunction "29_29") (pintype "passive"))
      (node (ref "U1") (pin "14") (pinfunction "GPIOL_25_CLK1_14") (pintype "passive"))
    )
    (net (code "58") (name "/GPIO6") (class "Default")
      (node (ref "D1") (pin "1") (pinfunction "A1_1") (pintype "passive"))
      (node (ref "PI") (pin "31") (pinfunction "31_31") (pintype "passive"))
      (node (ref "U1") (pin "144") (pinfunction "GPIOL_64_144") (pintype "passive"))
    )
    (net (code "59") (name "/GPIO7") (class "Default")
      (node (ref "D1") (pin "2") (pinfunction "A2_2") (pintype "passive"))
      (node (ref "PI") (pin "26") (pinfunction "26_26") (pintype "passive"))
      (node (ref "U1") (pin "3") (pinfunction "GPIOL_53_CDI10_3") (pintype "passive"))
    )
    (net (code "60") (name "/GPIO8") (class "Default")
      (node (ref "PI") (pin "24") (pinfunction "24_24") (pintype "passive"))
      (node (ref "U1") (pin "19") (pinfunction "GPIOL_13_CDI3_19") (pintype "passive"))
    )
    (net (code "61") (name "/GPIO9") (class "Default")
      (node (ref "PI") (pin "21") (pinfunction "21_21") (pintype "passive"))
      (node (ref "U1") (pin "20") (pinfunction "GPIOL_12_CDI2_20") (pintype "passive"))
    )
    (net (code "62") (name "/GPIO10") (class "Default")
      (node (ref "PI") (pin "19") (pinfunction "19_19") (pintype "passive"))
      (node (ref "U1") (pin "29") (pinfunction "GPIOL_08_CDI0_29") (pintype "passive"))
    )
    (net (code "63") (name "/GPIO11") (class "Default")
      (node (ref "PI") (pin "23") (pinfunction "23_23") (pintype "passive"))
      (node (ref "U1") (pin "18") (pinfunction "GPIOL_20_CTRL0_CDI4_18") (pintype "passive"))
    )
    (net (code "64") (name "/GPIO12") (class "Default")
      (node (ref "PI") (pin "32") (pinfunction "32_32") (pintype "passive"))
      (node (ref "U1") (pin "15") (pinfunction "GPIOL_24_CLK0_15") (pintype "passive"))
    )
    (net (code "65") (name "/GPIO13") (class "Default")
      (node (ref "PI") (pin "33") (pinfunction "33_33") (pintype "passive"))
      (node (ref "U1") (pin "10") (pinfunction "GPIOL_32_CTRL4_CDI7_10") (pintype "passive"))
    )
    (net (code "66") (name "/GPIO14") (class "Default")
      (node (ref "PI") (pin "8") (pinfunction "8_8") (pintype "passive"))
      (node (ref "U1") (pin "78") (pinfunction "GPIOR_151_CBUS0_78") (pintype "passive"))
    )
    (net (code "67") (name "/GPIO15") (class "Default")
      (node (ref "PI") (pin "10") (pinfunction "10_10") (pintype "passive"))
      (node (ref "U1") (pin "79") (pinfunction "GPIOR_150_CBUS1_79") (pintype "passive"))
    )
    (net (code "68") (name "/GPIO16") (class "Default")
      (node (ref "PI") (pin "36") (pinfunction "36_36") (pintype "passive"))
      (node (ref "U1") (pin "11") (pinfunction "GPIOL_31_CLK7_CDI6_11") (pintype "passive"))
    )
    (net (code "69") (name "/GPIO17") (class "Default")
      (node (ref "PI") (pin "11") (pinfunction "11_11") (pintype "passive"))
      (node (ref "R3") (pin "1") (pintype "passive"))
      (node (ref "U1") (pin "74") (pinfunction "GPIOR_158_TESTN_74") (pintype "passive"))
    )
    (net (code "70") (name "/GPIO18") (class "Default")
      (node (ref "PI") (pin "12") (pinfunction "12_12") (pintype "passive"))
      (node (ref "U1") (pin "80") (pinfunction "GPIOR_149_CBUS2_80") (pintype "passive"))
    )
    (net (code "71") (name "/GPIO19") (class "Default")
      (node (ref "PI") (pin "35") (pinfunction "35_35") (pintype "passive"))
      (node (ref "U1") (pin "7") (pinfunction "GPIOL_41_CDI9_7") (pintype "passive"))
    )
    (net (code "72") (name "/GPIO20") (class "Default")
      (node (ref "PI") (pin "38") (pinfunction "38_38") (pintype "passive"))
      (node (ref "U1") (pin "8") (pinfunction "GPIOL_40_CDI8_8") (pintype "passive"))
    )
    (net (code "73") (name "/GPIO21") (class "Default")
      (node (ref "PI") (pin "40") (pinfunction "40_40") (pintype "passive"))
      (node (ref "U1") (pin "6") (pinfunction "GPIOL_46_6") (pintype "passive"))
    )
    (net (code "74") (name "/GPIO22") (class "Default")
      (node (ref "PI") (pin "15") (pinfunction "15_15") (pintype "passive"))
      (node (ref "U1") (pin "30") (pinfunction "GPIOL_01_CCK_30") (pintype "passive"))
    )
    (net (code "75") (name "/GPIO23") (class "Default")
      (node (ref "PI") (pin "16") (pinfunction "16_16") (pintype "passive"))
      (node (ref "U1") (pin "32") (pinfunction "GPIOL_04_CSI_32") (pintype "passive"))
    )
    (net (code "76") (name "/GPIO24") (class "Default")
      (node (ref "PI") (pin "18") (pinfunction "18_18") (pintype "passive"))
      (node (ref "R13") (pin "2") (pintype "passive"))
      (node (ref "U1") (pin "31") (pinfunction "GPIOL_00_SS_31") (pintype "passive"))
    )
    (net (code "77") (name "/GPIO25") (class "Default")
      (node (ref "PI") (pin "22") (pinfunction "22_22") (pintype "passive"))
      (node (ref "U1") (pin "28") (pinfunction "GPIOL_09_CDI1_28") (pintype "passive"))
    )
    (net (code "78") (name "/GPIO26") (class "Default")
      (node (ref "PI") (pin "37") (pinfunction "37_37") (pintype "passive"))
      (node (ref "U1") (pin "4") (pinfunction "GPIOL_54_CDI11_4") (pintype "passive"))
    )
    (net (code "79") (name "/GPIO27") (class "Default")
      (node (ref "PI") (pin "13") (pinfunction "13_13") (pintype "passive"))
      (node (ref "U1") (pin "33") (pinfunction "GPIOL_05_CSO_33") (pintype "passive"))
    )
    (net (code "80") (name "/HIZ_CTRL") (class "Default")
      (node (ref "R16") (pin "2") (pinfunction "2_2") (pintype "passive"))
      (node (ref "U1") (pin "93") (pinfunction "GPIOR_123_CLK12_CDI20_93") (pintype "passive"))
      (node (ref "U5") (pin "13") (pinfunction "~{OE}2_13") (pintype "input"))
      (node (ref "U6") (pin "1") (pinfunction "~{OE}1_1") (pintype "input"))
      (node (ref "U6") (pin "13") (pinfunction "~{OE}2_13") (pintype "input"))
      (node (ref "U7") (pin "1") (pinfunction "~{OE}1_1") (pintype "input"))
      (node (ref "U7") (pin "13") (pinfunction "~{OE}2_13") (pintype "input"))
    )
    (net (code "81") (name "/HIZ_DATA") (class "Default")
      (node (ref "R17") (pin "2") (pinfunction "2_2") (pintype "passive"))
      (node (ref "U1") (pin "92") (pinfunction "GPIOR_125_CLK10_92") (pintype "passive"))
      (node (ref "U2") (pin "1") (pinfunction "~{OE}1_1") (pintype "input"))
      (node (ref "U2") (pin "13") (pinfunction "~{OE}2_13") (pintype "input"))
      (node (ref "U3") (pin "1") (pinfunction "~{OE}1_1") (pintype "input"))
      (node (ref "U3") (pin "13") (pinfunction "~{OE}2_13") (pintype "input"))
      (node (ref "U4") (pin "1") (pinfunction "~{OE}1_1") (pintype "input"))
      (node (ref "U4") (pin "13") (pinfunction "~{OE}2_13") (pintype "input"))
      (node (ref "U5") (pin "1") (pinfunction "~{OE}1_1") (pintype "input"))
    )
    (net (code "82") (name "/HLT") (class "Default")
      (node (ref "U1") (pin "131") (pinfunction "GPIOL_75_PLLIN1_131") (pintype "passive"))
      (node (ref "U5") (pin "15") (pinfunction "2B1_15") (pintype "bidirectional"))
    )
    (net (code "83") (name "/INT2") (class "Default")
      (node (ref "U1") (pin "132") (pinfunction "GPIOL_74_PLLIN0_132") (pintype "passive"))
      (node (ref "U7") (pin "20") (pinfunction "2B4_20") (pintype "bidirectional"))
    )
    (net (code "84") (name "/INT6") (class "Default")
      (node (ref "U1") (pin "134") (pinfunction "GPIOL_73_EXTFB1_CDI15_134") (pintype "passive"))
      (node (ref "U7") (pin "23") (pinfunction "2B5_23") (pintype "bidirectional"))
    )
    (net (code "85") (name "/IPL0") (class "Default")
      (node (ref "U1") (pin "118") (pinfunction "GPIOR_79_EXTFB1_CDI30_118") (pintype "passive"))
      (node (ref "U5") (pin "19") (pinfunction "2B3_19") (pintype "bidirectional"))
    )
    (net (code "86") (name "/IPL1") (class "Default")
      (node (ref "U1") (pin "117") (pinfunction "GPIOR_80_117") (pintype "passive"))
      (node (ref "U5") (pin "20") (pinfunction "2B4_20") (pintype "bidirectional"))
    )
    (net (code "87") (name "/IPL2") (class "Default")
      (node (ref "U1") (pin "116") (pinfunction "GPIOR_81_MREFCLK_116") (pintype "passive"))
      (node (ref "U5") (pin "23") (pinfunction "2B5_23") (pintype "bidirectional"))
    )
    (net (code "88") (name "/KB_RESET") (class "Default")
      (node (ref "U1") (pin "110") (pinfunction "GPIOR_87_CDI29_110") (pintype "passive"))
      (node (ref "U7") (pin "15") (pinfunction "2B1_15") (pintype "bidirectional"))
    )
    (net (code "89") (name "/P58") (class "Default")
      (node (ref "CN1") (pin "P$58") (pinfunction "D16_P58_P$58") (pintype "passive"))
      (node (ref "RN4") (pin "8") (pinfunction "8_8") (pintype "passive"))
      (node (ref "U3") (pin "22") (pinfunction "2A5_22") (pintype "bidirectional"))
    )
    (net (code "90") (name "/P61") (class "Default")
      (node (ref "CN1") (pin "P$61") (pinfunction "D15_P61_P$61") (pintype "passive"))
      (node (ref "RN5") (pin "5") (pinfunction "5_5") (pintype "passive"))
      (node (ref "U3") (pin "21") (pinfunction "2A4_21") (pintype "bidirectional"))
    )
    (net (code "91") (name "/P62") (class "Default")
      (node (ref "CN1") (pin "P$62") (pinfunction "D14_P62_P$62") (pintype "passive"))
      (node (ref "RN5") (pin "6") (pinfunction "6_6") (pintype "passive"))
      (node (ref "U3") (pin "18") (pinfunction "2A3_18") (pintype "bidirectional"))
    )
    (net (code "92") (name "/P63") (class "Default")
      (node (ref "CN1") (pin "P$63") (pinfunction "D13_P63_P$63") (pintype "passive"))
      (node (ref "RN5") (pin "7") (pinfunction "7_7") (pintype "passive"))
      (node (ref "U3") (pin "17") (pinfunction "2A2_17") (pintype "bidirectional"))
    )
    (net (code "93") (name "/P64") (class "Default")
      (node (ref "CN1") (pin "P$64") (pinfunction "D12_P64_P$64") (pintype "passive"))
      (node (ref "RN5") (pin "8") (pinfunction "8_8") (pintype "passive"))
      (node (ref "U3") (pin "14") (pinfunction "2A1_14") (pintype "bidirectional"))
    )
    (net (code "94") (name "/P65") (class "Default")
      (node (ref "CN1") (pin "P$65") (pinfunction "D11_P65_P$65") (pintype "passive"))
      (node (ref "RN6") (pin "5") (pinfunction "5_5") (pintype "passive"))
      (node (ref "U4") (pin "11") (pinfunction "1A5_11") (pintype "bidirectional"))
    )
    (net (code "95") (name "/P66") (class "Default")
      (node (ref "CN1") (pin "P$66") (pinfunction "D10_P66_P$66") (pintype "passive"))
      (node (ref "RN6") (pin "6") (pinfunction "6_6") (pintype "passive"))
      (node (ref "U4") (pin "8") (pinfunction "1A4_8") (pintype "bidirectional"))
    )
    (net (code "96") (name "/P67") (class "Default")
      (node (ref "CN1") (pin "P$67") (pinfunction "D9_P67_P$67") (pintype "passive"))
      (node (ref "RN6") (pin "7") (pinfunction "7_7") (pintype "passive"))
      (node (ref "U4") (pin "7") (pinfunction "1A3_7") (pintype "bidirectional"))
    )
    (net (code "97") (name "/P68") (class "Default")
      (node (ref "CN1") (pin "P$68") (pinfunction "D8_P68_P$68") (pintype "passive"))
      (node (ref "RN6") (pin "8") (pinfunction "8_8") (pintype "passive"))
      (node (ref "U4") (pin "4") (pinfunction "1A2_4") (pintype "bidirectional"))
    )
    (net (code "98") (name "/P71") (class "Default")
      (node (ref "CN1") (pin "P$71") (pinfunction "D7_P71_P$71") (pintype "passive"))
      (node (ref "RN7") (pin "5") (pinfunction "5_5") (pintype "passive"))
      (node (ref "U4") (pin "3") (pinfunction "1A1_3") (pintype "bidirectional"))
    )
    (net (code "99") (name "/P72") (class "Default")
      (node (ref "CN1") (pin "P$72") (pinfunction "D6_P72_P$72") (pintype "passive"))
      (node (ref "RN7") (pin "6") (pinfunction "6_6") (pintype "passive"))
      (node (ref "U4") (pin "22") (pinfunction "2A5_22") (pintype "bidirectional"))
    )
    (net (code "100") (name "/P73") (class "Default")
      (node (ref "CN1") (pin "P$73") (pinfunction "D5_P73_P$73") (pintype "passive"))
      (node (ref "RN7") (pin "7") (pinfunction "7_7") (pintype "passive"))
      (node (ref "U4") (pin "21") (pinfunction "2A4_21") (pintype "bidirectional"))
    )
    (net (code "101") (name "/P74") (class "Default")
      (node (ref "CN1") (pin "P$74") (pinfunction "D4_P74_P$74") (pintype "passive"))
      (node (ref "RN7") (pin "8") (pinfunction "8_8") (pintype "passive"))
      (node (ref "U4") (pin "18") (pinfunction "2A3_18") (pintype "bidirectional"))
    )
    (net (code "102") (name "/P75") (class "Default")
      (node (ref "CN1") (pin "P$75") (pinfunction "D3_P75_P$75") (pintype "passive"))
      (node (ref "RN8") (pin "5") (pinfunction "5_5") (pintype "passive"))
      (node (ref "U4") (pin "17") (pinfunction "2A2_17") (pintype "bidirectional"))
    )
    (net (code "103") (name "/P76") (class "Default")
      (node (ref "CN1") (pin "P$76") (pinfunction "D2_P76_P$76") (pintype "passive"))
      (node (ref "RN8") (pin "6") (pinfunction "6_6") (pintype "passive"))
      (node (ref "U4") (pin "14") (pinfunction "2A1_14") (pintype "bidirectional"))
    )
    (net (code "104") (name "/P77") (class "Default")
      (node (ref "CN1") (pin "P$77") (pinfunction "D1_P77_P$77") (pintype "passive"))
      (node (ref "RN8") (pin "7") (pinfunction "7_7") (pintype "passive"))
      (node (ref "U5") (pin "3") (pinfunction "1A1_3") (pintype "bidirectional"))
    )
    (net (code "105") (name "/P78") (class "Default")
      (node (ref "CN1") (pin "P$78") (pinfunction "D0_P78_P$78") (pintype "passive"))
      (node (ref "RN8") (pin "8") (pinfunction "8_8") (pintype "passive"))
      (node (ref "U5") (pin "4") (pinfunction "1A2_4") (pintype "bidirectional"))
    )
    (net (code "106") (name "/P81") (class "Default")
      (node (ref "CN1") (pin "P$81") (pinfunction "ILP2_P81_P$81") (pintype "passive"))
      (node (ref "U5") (pin "22") (pinfunction "2A5_22") (pintype "bidirectional"))
    )
    (net (code "107") (name "/P82") (class "Default")
      (node (ref "CN1") (pin "P$82") (pinfunction "IPL1_P82_P$82") (pintype "passive"))
      (node (ref "U5") (pin "21") (pinfunction "2A4_21") (pintype "bidirectional"))
    )
    (net (code "108") (name "/P83") (class "Default")
      (node (ref "CN1") (pin "P$83") (pinfunction "IPL0_P83_P$83") (pintype "passive"))
      (node (ref "U5") (pin "18") (pinfunction "2A3_18") (pintype "bidirectional"))
    )
    (net (code "109") (name "/P84") (class "Default")
      (node (ref "CN1") (pin "P$84") (pinfunction "!IPEND!(NC)_P84_P$84") (pintype "passive"))
    )
    (net (code "110") (name "/P85") (class "Default")
      (node (ref "CN1") (pin "P$85") (pinfunction "!RST!_P85_P$85") (pintype "passive"))
      (node (ref "U5") (pin "17") (pinfunction "2A2_17") (pintype "bidirectional"))
    )
    (net (code "111") (name "/P86") (class "Default")
      (node (ref "CN1") (pin "P$86") (pinfunction "!HLT!_P86_P$86") (pintype "passive"))
      (node (ref "U5") (pin "14") (pinfunction "2A1_14") (pintype "bidirectional"))
    )
    (net (code "112") (name "/P87") (class "Default")
      (node (ref "CN1") (pin "P$87") (pinfunction "!ECS!(NC)_P87_P$87") (pintype "passive"))
    )
    (net (code "113") (name "/P88") (class "Default")
      (node (ref "CN1") (pin "P$88") (pinfunction "!OCS!(NC)_P88_P$88") (pintype "passive"))
    )
    (net (code "114") (name "/P89") (class "Default")
      (node (ref "CN1") (pin "P$89") (pinfunction "SIZ1_P89_P$89") (pintype "passive"))
      (node (ref "U6") (pin "11") (pinfunction "1A5_11") (pintype "bidirectional"))
    )
    (net (code "115") (name "/P90") (class "Default")
      (node (ref "CN1") (pin "P$90") (pinfunction "SIZ0_P90_P$90") (pintype "passive"))
      (node (ref "U6") (pin "8") (pinfunction "1A4_8") (pintype "bidirectional"))
    )
    (net (code "116") (name "/P91") (class "Default")
      (node (ref "CN1") (pin "P$91") (pinfunction "!AS!_P91_P$91") (pintype "passive"))
      (node (ref "U6") (pin "7") (pinfunction "1A3_7") (pintype "bidirectional"))
    )
    (net (code "117") (name "/P92") (class "Default")
      (node (ref "CN1") (pin "P$92") (pinfunction "!DS!_P92_P$92") (pintype "passive"))
      (node (ref "U6") (pin "4") (pinfunction "1A2_4") (pintype "bidirectional"))
    )
    (net (code "118") (name "/P93") (class "Default")
      (node (ref "CN1") (pin "P$93") (pinfunction "RW_P93_P$93") (pintype "passive"))
      (node (ref "U6") (pin "3") (pinfunction "1A1_3") (pintype "bidirectional"))
    )
    (net (code "119") (name "/P94") (class "Default")
      (node (ref "CN1") (pin "P$94") (pinfunction "!BERR!_P94_P$94") (pintype "passive"))
      (node (ref "U6") (pin "22") (pinfunction "2A5_22") (pintype "bidirectional"))
    )
    (net (code "120") (name "/P95") (class "Default")
      (node (ref "CN1") (pin "P$95") (pinfunction "!STERM!(NC)_P95_P$95") (pintype "passive"))
    )
    (net (code "121") (name "/P96") (class "Default")
      (node (ref "CN1") (pin "P$96") (pinfunction "!AVEC!_P96_P$96") (pintype "passive"))
      (node (ref "U6") (pin "14") (pinfunction "2A1_14") (pintype "bidirectional"))
    )
    (net (code "122") (name "/P97") (class "Default")
      (node (ref "CN1") (pin "P$97") (pinfunction "!DSACK1!_P97_P$97") (pintype "passive"))
      (node (ref "U6") (pin "21") (pinfunction "2A4_21") (pintype "bidirectional"))
    )
    (net (code "123") (name "/P98") (class "Default")
      (node (ref "CN1") (pin "P$98") (pinfunction "!DSACK0!_P98_P$98") (pintype "passive"))
      (node (ref "U6") (pin "18") (pinfunction "2A3_18") (pintype "bidirectional"))
    )
    (net (code "124") (name "/P99") (class "Default")
      (node (ref "CN1") (pin "P$99") (pinfunction "CPU_CLK_P99_P$99") (pintype "passive"))
      (node (ref "U6") (pin "17") (pinfunction "2A2_17") (pintype "bidirectional"))
    )
    (net (code "125") (name "/P100") (class "Default")
      (node (ref "CN1") (pin "P$100") (pinfunction "E_P100_P$100") (pintype "passive"))
    )
    (net (code "126") (name "/P103") (class "Default")
      (node (ref "CN1") (pin "P$103") (pinfunction "FC2_P103_P$103") (pintype "passive"))
      (node (ref "U7") (pin "11") (pinfunction "1A5_11") (pintype "bidirectional"))
    )
    (net (code "127") (name "/P104") (class "Default")
      (node (ref "CN1") (pin "P$104") (pinfunction "FC1_P104_P$104") (pintype "passive"))
      (node (ref "U7") (pin "8") (pinfunction "1A4_8") (pintype "bidirectional"))
    )
    (net (code "128") (name "/P105") (class "Default")
      (node (ref "CN1") (pin "P$105") (pinfunction "FC0_P105_P$105") (pintype "passive"))
      (node (ref "U7") (pin "7") (pinfunction "1A3_7") (pintype "bidirectional"))
    )
    (net (code "129") (name "/P106") (class "Default")
      (node (ref "CN1") (pin "P$106") (pinfunction "!RMC!_P106_P$106") (pintype "passive"))
    )
    (net (code "130") (name "/P107") (class "Default")
      (node (ref "CN1") (pin "P$107") (pinfunction "!CIIN!(NC)_P107_P$107") (pintype "passive"))
    )
    (net (code "131") (name "/P108") (class "Default")
      (node (ref "CN1") (pin "P$108") (pinfunction "!CIOUT!(NC)_P108_P$108") (pintype "passive"))
    )
    (net (code "132") (name "/P109") (class "Default")
      (node (ref "CN1") (pin "P$109") (pinfunction "!CBREQ!(NC)_109_P$109") (pintype "passive"))
    )
    (net (code "133") (name "/P110") (class "Default")
      (node (ref "CN1") (pin "P$110") (pinfunction "!CBACK!(NC)_P110_P$110") (pintype "passive"))
    )
    (net (code "134") (name "/P111") (class "Default")
      (node (ref "CN1") (pin "P$111") (pinfunction "!BR!_P111_P$111") (pintype "passive"))
      (node (ref "R4") (pin "1") (pintype "passive"))
      (node (ref "U7") (pin "4") (pinfunction "1A2_4") (pintype "bidirectional"))
    )
    (net (code "135") (name "/P112") (class "Default")
      (node (ref "CN1") (pin "P$112") (pinfunction "!BG!_P112_P$112") (pintype "passive"))
      (node (ref "U7") (pin "3") (pinfunction "1A1_3") (pintype "bidirectional"))
    )
    (net (code "136") (name "/P113") (class "Default")
      (node (ref "CN1") (pin "P$113") (pinfunction "!BGACK!(NC)_P113_P$113") (pintype "passive"))
      (node (ref "U7") (pin "18") (pinfunction "2A3_18") (pintype "bidirectional"))
    )
    (net (code "137") (name "/P114") (class "Default")
      (node (ref "CN1") (pin "P$114") (pinfunction "!BOSS!_P114_P$114") (pintype "passive"))
    )
    (net (code "138") (name "/P115") (class "Default")
      (node (ref "CN1") (pin "P$115") (pinfunction "!FPU_CS!_P115_P$115") (pintype "passive"))
    )
    (net (code "139") (name "/P116") (class "Default")
      (node (ref "CN1") (pin "P$116") (pinfunction "!FPU_SENSE!_P116_P$116") (pintype "passive"))
    )
    (net (code "140") (name "/P117") (class "Default")
      (node (ref "CN1") (pin "P$117") (pinfunction "CCK_P117_P$117") (pintype "passive"))
    )
    (net (code "141") (name "/P118") (class "Default")
      (node (ref "CN1") (pin "P$118") (pinfunction "!RESET!_P118_P$118") (pintype "passive"))
      (node (ref "U7") (pin "17") (pinfunction "2A2_17") (pintype "bidirectional"))
    )
    (net (code "142") (name "/P121") (class "Default")
      (node (ref "CN1") (pin "P$121") (pinfunction "!NET_CS!_P121_P$121") (pintype "passive"))
    )
    (net (code "143") (name "/P122") (class "Default")
      (node (ref "CN1") (pin "P$122") (pinfunction "!SPARE_CS!_P122_P$122") (pintype "passive"))
    )
    (net (code "144") (name "/P123") (class "Default")
      (node (ref "CN1") (pin "P$123") (pinfunction "!RTC_CS!_P123_P$123") (pintype "passive"))
    )
    (net (code "145") (name "/P124") (class "Default")
      (node (ref "CN1") (pin "P$124") (pinfunction "!FLASH!_P124_P$124") (pintype "passive"))
    )
    (net (code "146") (name "/P125") (class "Default")
      (node (ref "CN1") (pin "P$125") (pinfunction "!REG!_P125_P$125") (pintype "passive"))
    )
    (net (code "147") (name "/P126") (class "Default")
      (node (ref "CN1") (pin "P$126") (pinfunction "!CC_ENA!_P126_P$126") (pintype "passive"))
    )
    (net (code "148") (name "/P127") (class "Default")
      (node (ref "CN1") (pin "P$127") (pinfunction "!WAIT!_P127_P$127") (pintype "passive"))
    )
    (net (code "149") (name "/P128") (class "Default")
      (node (ref "CN1") (pin "P$128") (pinfunction "!KB_RESET!_P128_P$128") (pintype "passive"))
      (node (ref "U7") (pin "14") (pinfunction "2A1_14") (pintype "bidirectional"))
    )
    (net (code "150") (name "/P129") (class "Default")
      (node (ref "CN1") (pin "P$129") (pinfunction "!IORDY!_P129_P$129") (pintype "passive"))
    )
    (net (code "151") (name "/P130") (class "Default")
      (node (ref "CN1") (pin "P$130") (pinfunction "!IOWR!_P130_P$130") (pintype "passive"))
    )
    (net (code "152") (name "/P131") (class "Default")
      (node (ref "CN1") (pin "P$131") (pinfunction "!OE!_P131_P$131") (pintype "passive"))
    )
    (net (code "153") (name "/P132") (class "Default")
      (node (ref "CN1") (pin "P$132") (pinfunction "!WE!_P132_P$132") (pintype "passive"))
    )
    (net (code "154") (name "/P133") (class "Default")
      (node (ref "CN1") (pin "P$133") (pinfunction "!OVR!_P133_P$133") (pintype "passive"))
    )
    (net (code "155") (name "/P134") (class "Default")
      (node (ref "CN1") (pin "P$134") (pinfunction "XRDY_P134_P$134") (pintype "passive"))
    )
    (net (code "156") (name "/P135") (class "Default")
      (node (ref "CN1") (pin "P$135") (pinfunction "!ZORRO!_P135_P$135") (pintype "passive"))
    )
    (net (code "157") (name "/P136") (class "Default")
      (node (ref "CN1") (pin "P$136") (pinfunction "!WIDE!_P136_P$136") (pintype "passive"))
    )
    (net (code "158") (name "/P137") (class "Default")
      (node (ref "CN1") (pin "P$137") (pinfunction "!INT2!_P137_P$137") (pintype "passive"))
      (node (ref "U7") (pin "21") (pinfunction "2A4_21") (pintype "bidirectional"))
    )
    (net (code "159") (name "/P138") (class "Default")
      (node (ref "CN1") (pin "P$138") (pinfunction "!INT6!_P138_P$138") (pintype "passive"))
      (node (ref "U7") (pin "22") (pinfunction "2A5_22") (pintype "bidirectional"))
    )
    (net (code "160") (name "/P141") (class "Default")
      (node (ref "CN1") (pin "P$141") (pinfunction "SYSTEM1_P141_P$141") (pintype "passive"))
    )
    (net (code "161") (name "/P142") (class "Default")
      (node (ref "CN1") (pin "P$142") (pinfunction "SYSTEM0_P142_P$142") (pintype "passive"))
    )
    (net (code "162") (name "/P143") (class "Default")
      (node (ref "CN1") (pin "P$143") (pinfunction "!XRXD!_P143_P$143") (pintype "passive"))
    )
    (net (code "163") (name "/P144") (class "Default")
      (node (ref "CN1") (pin "P$144") (pinfunction "!XTXD!_P144_P$144") (pintype "passive"))
    )
    (net (code "164") (name "/P145") (class "Default")
      (node (ref "CN1") (pin "P$145") (pinfunction "!CFOUT!_P145_P$145") (pintype "passive"))
    )
    (net (code "165") (name "/PS1") (class "Default")
      (node (ref "CN1") (pin "P$1") (pinfunction "A31_P1_P$1") (pintype "passive"))
      (node (ref "U11") (pin "19") (pinfunction "Q1_19") (pintype "tri_state"))
    )
    (net (code "166") (name "/PS2") (class "Default")
      (node (ref "CN1") (pin "P$2") (pinfunction "A30_P2_P$2") (pintype "passive"))
      (node (ref "U11") (pin "18") (pinfunction "Q2_18") (pintype "tri_state"))
    )
    (net (code "167") (name "/PS3") (class "Default")
      (node (ref "CN1") (pin "P$3") (pinfunction "A29_P3_P$3") (pintype "passive"))
      (node (ref "U11") (pin "17") (pinfunction "Q3_17") (pintype "tri_state"))
    )
    (net (code "168") (name "/PS4") (class "Default")
      (node (ref "CN1") (pin "P$4") (pinfunction "A28_P4_P$4") (pintype "passive"))
      (node (ref "U11") (pin "16") (pinfunction "Q4_16") (pintype "tri_state"))
    )
    (net (code "169") (name "/PS5") (class "Default")
      (node (ref "CN1") (pin "P$5") (pinfunction "A27_P5_P$5") (pintype "passive"))
      (node (ref "U11") (pin "15") (pinfunction "Q5_15") (pintype "tri_state"))
    )
    (net (code "170") (name "/PS6") (class "Default")
      (node (ref "CN1") (pin "P$6") (pinfunction "A26_P6_P$6") (pintype "passive"))
      (node (ref "U11") (pin "14") (pinfunction "Q6_14") (pintype "tri_state"))
    )
    (net (code "171") (name "/PS7") (class "Default")
      (node (ref "CN1") (pin "P$7") (pinfunction "A25_P7_P$7") (pintype "passive"))
      (node (ref "U11") (pin "13") (pinfunction "Q7_13") (pintype "tri_state"))
    )
    (net (code "172") (name "/PS8") (class "Default")
      (node (ref "CN1") (pin "P$8") (pinfunction "A24_P8_P$8") (pintype "passive"))
      (node (ref "U11") (pin "12") (pinfunction "Q8_12") (pintype "tri_state"))
    )
    (net (code "173") (name "/PS11") (class "Default")
      (node (ref "CN1") (pin "P$11") (pinfunction "A23_P11_P$11") (pintype "passive"))
      (node (ref "U10") (pin "19") (pinfunction "Q1_19") (pintype "tri_state"))
    )
    (net (code "174") (name "/PS12") (class "Default")
      (node (ref "CN1") (pin "P$12") (pinfunction "A22_P12_P$12") (pintype "passive"))
      (node (ref "U10") (pin "18") (pinfunction "Q2_18") (pintype "tri_state"))
    )
    (net (code "175") (name "/PS13") (class "Default")
      (node (ref "CN1") (pin "P$13") (pinfunction "A21_P13_P$13") (pintype "passive"))
      (node (ref "U10") (pin "17") (pinfunction "Q3_17") (pintype "tri_state"))
    )
    (net (code "176") (name "/PS14") (class "Default")
      (node (ref "CN1") (pin "P$14") (pinfunction "A20_P14_P$14") (pintype "passive"))
      (node (ref "U10") (pin "16") (pinfunction "Q4_16") (pintype "tri_state"))
    )
    (net (code "177") (name "/PS15") (class "Default")
      (node (ref "CN1") (pin "P$15") (pinfunction "A19_P15_P$15") (pintype "passive"))
      (node (ref "U8") (pin "12") (pinfunction "Q8_12") (pintype "tri_state"))
    )
    (net (code "178") (name "/PS16") (class "Default")
      (node (ref "CN1") (pin "P$16") (pinfunction "A18_P16_P$16") (pintype "passive"))
      (node (ref "U8") (pin "13") (pinfunction "Q7_13") (pintype "tri_state"))
    )
    (net (code "179") (name "/PS17") (class "Default")
      (node (ref "CN1") (pin "P$17") (pinfunction "A17_P17_P$17") (pintype "passive"))
      (node (ref "U8") (pin "14") (pinfunction "Q6_14") (pintype "tri_state"))
    )
    (net (code "180") (name "/PS18") (class "Default")
      (node (ref "CN1") (pin "P$18") (pinfunction "A16_P18_P$18") (pintype "passive"))
      (node (ref "U8") (pin "15") (pinfunction "Q5_15") (pintype "tri_state"))
    )
    (net (code "181") (name "/PS21") (class "Default")
      (node (ref "CN1") (pin "P$21") (pinfunction "A15_P21_P$21") (pintype "passive"))
      (node (ref "U8") (pin "16") (pinfunction "Q4_16") (pintype "tri_state"))
    )
    (net (code "182") (name "/PS22") (class "Default")
      (node (ref "CN1") (pin "P$22") (pinfunction "A14_P22_P$22") (pintype "passive"))
      (node (ref "U8") (pin "17") (pinfunction "Q3_17") (pintype "tri_state"))
    )
    (net (code "183") (name "/PS23") (class "Default")
      (node (ref "CN1") (pin "P$23") (pinfunction "A13_P23_P$23") (pintype "passive"))
      (node (ref "U8") (pin "18") (pinfunction "Q2_18") (pintype "tri_state"))
    )
    (net (code "184") (name "/PS24") (class "Default")
      (node (ref "CN1") (pin "P$24") (pinfunction "A12_P24_P$24") (pintype "passive"))
      (node (ref "U8") (pin "19") (pinfunction "Q1_19") (pintype "tri_state"))
    )
    (net (code "185") (name "/PS25") (class "Default")
      (node (ref "CN1") (pin "P$25") (pinfunction "A11_P25_P$25") (pintype "passive"))
      (node (ref "U10") (pin "15") (pinfunction "Q5_15") (pintype "tri_state"))
    )
    (net (code "186") (name "/PS26") (class "Default")
      (node (ref "CN1") (pin "P$26") (pinfunction "A10_P26_P$26") (pintype "passive"))
      (node (ref "U10") (pin "14") (pinfunction "Q6_14") (pintype "tri_state"))
    )
    (net (code "187") (name "/PS27") (class "Default")
      (node (ref "CN1") (pin "P$27") (pinfunction "A9_P27_P$27") (pintype "passive"))
      (node (ref "U10") (pin "13") (pinfunction "Q7_13") (pintype "tri_state"))
    )
    (net (code "188") (name "/PS28") (class "Default")
      (node (ref "CN1") (pin "P$28") (pinfunction "A8_P28_P$28") (pintype "passive"))
      (node (ref "U10") (pin "12") (pinfunction "Q8_12") (pintype "tri_state"))
    )
    (net (code "189") (name "/PS31") (class "Default")
      (node (ref "CN1") (pin "P$31") (pinfunction "A7_P31_P$31") (pintype "passive"))
      (node (ref "U9") (pin "19") (pinfunction "Q1_19") (pintype "tri_state"))
    )
    (net (code "190") (name "/PS32") (class "Default")
      (node (ref "CN1") (pin "P$32") (pinfunction "A6_P32_P$32") (pintype "passive"))
      (node (ref "U9") (pin "18") (pinfunction "Q2_18") (pintype "tri_state"))
    )
    (net (code "191") (name "/PS33") (class "Default")
      (node (ref "CN1") (pin "P$33") (pinfunction "A5_P33_P$33") (pintype "passive"))
      (node (ref "U9") (pin "17") (pinfunction "Q3_17") (pintype "tri_state"))
    )
    (net (code "192") (name "/PS34") (class "Default")
      (node (ref "CN1") (pin "P$34") (pinfunction "A4_P34_P$34") (pintype "passive"))
      (node (ref "U9") (pin "16") (pinfunction "Q4_16") (pintype "tri_state"))
    )
    (net (code "193") (name "/PS35") (class "Default")
      (node (ref "CN1") (pin "P$35") (pinfunction "A3_P35_P$35") (pintype "passive"))
      (node (ref "U9") (pin "15") (pinfunction "Q5_15") (pintype "tri_state"))
    )
    (net (code "194") (name "/PS36") (class "Default")
      (node (ref "CN1") (pin "P$36") (pinfunction "A2_P36_P$36") (pintype "passive"))
      (node (ref "U9") (pin "14") (pinfunction "Q6_14") (pintype "tri_state"))
    )
    (net (code "195") (name "/PS37") (class "Default")
      (node (ref "CN1") (pin "P$37") (pinfunction "A1_P37_P$37") (pintype "passive"))
      (node (ref "U9") (pin "13") (pinfunction "Q7_13") (pintype "tri_state"))
    )
    (net (code "196") (name "/PS38") (class "Default")
      (node (ref "CN1") (pin "P$38") (pinfunction "A0_P38_P$38") (pintype "passive"))
      (node (ref "U9") (pin "12") (pinfunction "Q8_12") (pintype "tri_state"))
    )
    (net (code "198") (name "/PS41") (class "Default")
      (node (ref "CN1") (pin "P$41") (pinfunction "D31_P41_P$41") (pintype "passive"))
      (node (ref "RN1") (pin "5") (pinfunction "5_5") (pintype "passive"))
      (node (ref "U2") (pin "11") (pinfunction "1A5_11") (pintype "bidirectional"))
    )
    (net (code "199") (name "/PS42") (class "Default")
      (node (ref "CN1") (pin "P$42") (pinfunction "D30_P42_P$42") (pintype "passive"))
      (node (ref "RN1") (pin "6") (pinfunction "6_6") (pintype "passive"))
      (node (ref "U2") (pin "8") (pinfunction "1A4_8") (pintype "bidirectional"))
    )
    (net (code "200") (name "/PS43") (class "Default")
      (node (ref "CN1") (pin "P$43") (pinfunction "D29_P43_P$43") (pintype "passive"))
      (node (ref "RN1") (pin "7") (pinfunction "7_7") (pintype "passive"))
      (node (ref "U2") (pin "7") (pinfunction "1A3_7") (pintype "bidirectional"))
    )
    (net (code "201") (name "/PS44") (class "Default")
      (node (ref "CN1") (pin "P$44") (pinfunction "D28_P44_P$44") (pintype "passive"))
      (node (ref "RN1") (pin "8") (pinfunction "8_8") (pintype "passive"))
      (node (ref "U2") (pin "4") (pinfunction "1A2_4") (pintype "bidirectional"))
    )
    (net (code "202") (name "/PS45") (class "Default")
      (node (ref "CN1") (pin "P$45") (pinfunction "D27_P45_P$45") (pintype "passive"))
      (node (ref "RN2") (pin "5") (pinfunction "5_5") (pintype "passive"))
      (node (ref "U2") (pin "3") (pinfunction "1A1_3") (pintype "bidirectional"))
    )
    (net (code "203") (name "/PS46") (class "Default")
      (node (ref "CN1") (pin "P$46") (pinfunction "D26_P46_P$46") (pintype "passive"))
      (node (ref "RN2") (pin "6") (pinfunction "6_6") (pintype "passive"))
      (node (ref "U2") (pin "22") (pinfunction "2A5_22") (pintype "bidirectional"))
    )
    (net (code "204") (name "/PS47") (class "Default")
      (node (ref "CN1") (pin "P$47") (pinfunction "D25_P47_P$47") (pintype "passive"))
      (node (ref "RN2") (pin "7") (pinfunction "7_7") (pintype "passive"))
      (node (ref "U2") (pin "21") (pinfunction "2A4_21") (pintype "bidirectional"))
    )
    (net (code "205") (name "/PS48") (class "Default")
      (node (ref "CN1") (pin "P$48") (pinfunction "D24_P48_P$48") (pintype "passive"))
      (node (ref "RN2") (pin "8") (pinfunction "8_8") (pintype "passive"))
      (node (ref "U2") (pin "18") (pinfunction "2A3_18") (pintype "bidirectional"))
    )
    (net (code "206") (name "/PS51") (class "Default")
      (node (ref "CN1") (pin "P$51") (pinfunction "D23_P51_P$51") (pintype "passive"))
      (node (ref "RN3") (pin "5") (pinfunction "5_5") (pintype "passive"))
      (node (ref "U2") (pin "17") (pinfunction "2A2_17") (pintype "bidirectional"))
    )
    (net (code "207") (name "/PS52") (class "Default")
      (node (ref "CN1") (pin "P$52") (pinfunction "D22_P52_P$52") (pintype "passive"))
      (node (ref "RN3") (pin "6") (pinfunction "6_6") (pintype "passive"))
      (node (ref "U2") (pin "14") (pinfunction "2A1_14") (pintype "bidirectional"))
    )
    (net (code "208") (name "/PS53") (class "Default")
      (node (ref "CN1") (pin "P$53") (pinfunction "D21_P53_P$53") (pintype "passive"))
      (node (ref "RN3") (pin "7") (pinfunction "7_7") (pintype "passive"))
      (node (ref "U3") (pin "11") (pinfunction "1A5_11") (pintype "bidirectional"))
    )
    (net (code "209") (name "/PS54") (class "Default")
      (node (ref "CN1") (pin "P$54") (pinfunction "D20_P54_P$54") (pintype "passive"))
      (node (ref "RN3") (pin "8") (pinfunction "8_8") (pintype "passive"))
      (node (ref "U3") (pin "8") (pinfunction "1A4_8") (pintype "bidirectional"))
    )
    (net (code "210") (name "/PS55") (class "Default")
      (node (ref "CN1") (pin "P$55") (pinfunction "D19_P55_P$55") (pintype "passive"))
      (node (ref "RN4") (pin "5") (pinfunction "5_5") (pintype "passive"))
      (node (ref "U3") (pin "7") (pinfunction "1A3_7") (pintype "bidirectional"))
    )
    (net (code "211") (name "/PS56") (class "Default")
      (node (ref "CN1") (pin "P$56") (pinfunction "D18_P56_P$56") (pintype "passive"))
      (node (ref "RN4") (pin "6") (pinfunction "6_6") (pintype "passive"))
      (node (ref "U3") (pin "4") (pinfunction "1A2_4") (pintype "bidirectional"))
    )
    (net (code "212") (name "/PS57") (class "Default")
      (node (ref "CN1") (pin "P$57") (pinfunction "D17_P57_P$57") (pintype "passive"))
      (node (ref "RN4") (pin "7") (pinfunction "7_7") (pintype "passive"))
      (node (ref "U3") (pin "3") (pinfunction "1A1_3") (pintype "bidirectional"))
    )
    (net (code "213") (name "/RESET") (class "Default")
      (node (ref "U1") (pin "109") (pinfunction "GPIOR_88_CDI28_109") (pintype "passive"))
      (node (ref "U7") (pin "16") (pinfunction "2B2_16") (pintype "bidirectional"))
    )
    (net (code "214") (name "/RST") (class "Default")
      (node (ref "U1") (pin "119") (pinfunction "GPIOR_78_EXTFB0_CDI31_119") (pintype "passive"))
      (node (ref "U5") (pin "16") (pinfunction "2B2_16") (pintype "bidirectional"))
    )
    (net (code "215") (name "/RW") (class "Default")
      (node (ref "U1") (pin "97") (pinfunction "GPIOR_122_CLK13_CDI21_97") (pintype "passive"))
      (node (ref "U6") (pin "2") (pinfunction "1B1_2") (pintype "bidirectional"))
    )
    (net (code "216") (name "/SIZ0") (class "Default")
      (node (ref "U1") (pin "100") (pinfunction "GPIOR_113_CDI22_100") (pintype "passive"))
      (node (ref "U6") (pin "9") (pinfunction "1B4_9") (pintype "bidirectional"))
    )
    (net (code "217") (name "/SIZ1") (class "Default")
      (node (ref "U1") (pin "101") (pinfunction "GPIOR_112_CDI23_101") (pintype "passive"))
      (node (ref "U6") (pin "10") (pinfunction "1B5_10") (pintype "bidirectional"))
    )
    (net (code "218") (name "/SPARE0") (class "Default")
      (node (ref "EXT") (pin "1") (pinfunction "1_1") (pintype "passive"))
      (node (ref "U1") (pin "135") (pinfunction "GPIOL_72_EXTFB0_CDI14_135") (pintype "passive"))
    )
    (net (code "219") (name "/SPARE1") (class "Default")
      (node (ref "EXT") (pin "2") (pinfunction "2_2") (pintype "passive"))
      (node (ref "U1") (pin "136") (pinfunction "GPIOL_71_NSTATUS_136") (pintype "passive"))
    )
    (net (code "220") (name "/SPARE2") (class "Default")
      (node (ref "EXT") (pin "3") (pinfunction "3_3") (pintype "passive"))
      (node (ref "U1") (pin "137") (pinfunction "GPIOL_70_CBSEL0_137") (pintype "passive"))
    )
    (net (code "221") (name "/SPARE3") (class "Default")
      (node (ref "EXT") (pin "4") (pinfunction "4_4") (pintype "passive"))
      (node (ref "U1") (pin "138") (pinfunction "GPIOL_69_CBSEL1_138") (pintype "passive"))
    )
    (net (code "222") (name "/SPARE4") (class "Default")
      (node (ref "EXT") (pin "5") (pinfunction "5_5") (pintype "passive"))
      (node (ref "U1") (pin "139") (pinfunction "GPIOL_68_139") (pintype "passive"))
    )
    (net (code "223") (name "/SPARE5") (class "Default")
      (node (ref "EXT") (pin "6") (pinfunction "6_6") (pintype "passive"))
      (node (ref "U1") (pin "140") (pinfunction "GPIOL_67_CDI13_140") (pintype "passive"))
    )
    (net (code "224") (name "/SPARE6") (class "Default")
      (node (ref "EXT") (pin "7") (pinfunction "7_7") (pintype "passive"))
      (node (ref "U1") (pin "141") (pinfunction "GPIOL_65_141") (pintype "passive"))
    )
    (net (code "225") (name "/SPARE7") (class "Default")
      (node (ref "EXT") (pin "8") (pinfunction "8_8") (pintype "passive"))
      (node (ref "U1") (pin "142") (pinfunction "GPIOL_66_CDI12_142") (pintype "passive"))
    )
    (net (code "226") (name "/TCK") (class "Default")
      (node (ref "JTAG") (pin "4") (pinfunction "4_4") (pintype "passive"))
      (node (ref "RN9") (pin "6") (pinfunction "6_6") (pintype "passive"))
      (node (ref "U1") (pin "26") (pinfunction "TCK_26") (pintype "passive"))
    )
    (net (code "227") (name "/TDI") (class "Default")
      (node (ref "JTAG") (pin "5") (pinfunction "5_5") (pintype "passive"))
      (node (ref "RN9") (pin "5") (pinfunction "5_5") (pintype "passive"))
      (node (ref "U1") (pin "27") (pinfunction "TDI_27") (pintype "passive"))
    )
    (net (code "228") (name "/TDO") (class "Default")
      (node (ref "JTAG") (pin "2") (pinfunction "2_2") (pintype "passive"))
      (node (ref "RN9") (pin "8") (pinfunction "8_8") (pintype "passive"))
      (node (ref "U1") (pin "24") (pinfunction "TDO_24") (pintype "passive"))
    )
    (net (code "229") (name "/TMS") (class "Default")
      (node (ref "JTAG") (pin "3") (pinfunction "3_3") (pintype "passive"))
      (node (ref "RN9") (pin "7") (pinfunction "7_7") (pintype "passive"))
      (node (ref "U1") (pin "25") (pinfunction "TMS_25") (pintype "passive"))
    )
    (net (code "230") (name "GND") (class "Default")
      (node (ref "C1") (pin "1") (pinfunction "1_1") (pintype "passive"))
      (node (ref "C10") (pin "1") (pinfunction "1_1") (pintype "passive"))
      (node (ref "C11") (pin "1") (pinfunction "1_1") (pintype "passive"))
      (node (ref "C12") (pin "1") (pinfunction "1_1") (pintype "passive"))
      (node (ref "C13") (pin "1") (pinfunction "1_1") (pintype "passive"))
      (node (ref "C14") (pin "1") (pinfunction "1_1") (pintype "passive"))
      (node (ref "C15") (pin "1") (pinfunction "1_1") (pintype "passive"))
      (node (ref "C16") (pin "1") (pinfunction "1_1") (pintype "passive"))
      (node (ref "C17") (pin "2") (pinfunction "2_2") (pintype "passive"))
      (node (ref "C18") (pin "2") (pinfunction "2_2") (pintype "passive"))
      (node (ref "C19") (pin "2") (pinfunction "2_2") (pintype "passive"))
      (node (ref "C2") (pin "1") (pinfunction "1_1") (pintype "passive"))
      (node (ref "C20") (pin "2") (pinfunction "2_2") (pintype "passive"))
      (node (ref "C21") (pin "2") (pinfunction "2_2") (pintype "passive"))
      (node (ref "C22") (pin "2") (pinfunction "2_2") (pintype "passive"))
      (node (ref "C23") (pin "2") (pinfunction "2_2") (pintype "passive"))
      (node (ref "C24") (pin "1") (pinfunction "1_1") (pintype "passive"))
      (node (ref "C3") (pin "1") (pinfunction "1_1") (pintype "passive"))
      (node (ref "C4") (pin "1") (pinfunction "1_1") (pintype "passive"))
      (node (ref "C5") (pin "1") (pinfunction "1_1") (pintype "passive"))
      (node (ref "C6") (pin "1") (pinfunction "1_1") (pintype "passive"))
      (node (ref "C7") (pin "1") (pinfunction "1_1") (pintype "passive"))
      (node (ref "C8") (pin "1") (pinfunction "1_1") (pintype "passive"))
      (node (ref "C9") (pin "1") (pinfunction "1_1") (pintype "passive"))
      (node (ref "CN1") (pin "P$101") (pinfunction "GND_P101_P$101") (pintype "passive"))
      (node (ref "CN1") (pin "P$119") (pinfunction "GND_P119_P$119") (pintype "passive"))
      (node (ref "CN1") (pin "P$139") (pinfunction "GND_P139_P$139") (pintype "passive"))
      (node (ref "CN1") (pin "P$146") (pinfunction "AGND_P146_P$146") (pintype "passive"))
      (node (ref "CN1") (pin "P$19") (pinfunction "GND_P19_P$19") (pintype "passive"))
      (node (ref "CN1") (pin "P$29") (pinfunction "GND_P29_P$29") (pintype "passive"))
      (node (ref "CN1") (pin "P$39") (pinfunction "GND_P39_P$39") (pintype "passive"))
      (node (ref "CN1") (pin "P$49") (pinfunction "GND_P49_P$49") (pintype "passive"))
      (node (ref "CN1") (pin "P$59") (pinfunction "GND_P59_P$59") (pintype "passive"))
      (node (ref "CN1") (pin "P$69") (pinfunction "GND_P69_P$69") (pintype "passive"))
      (node (ref "CN1") (pin "P$79") (pinfunction "GND_P79_P$79") (pintype "passive"))
      (node (ref "CN1") (pin "P$9") (pinfunction "GND_P9_P$9") (pintype "passive"))
      (node (ref "EXT") (pin "9") (pinfunction "9_9") (pintype "passive"))
      (node (ref "JTAG") (pin "6") (pinfunction "6_6") (pintype "passive"))
      (node (ref "M1") (pin "1") (pinfunction "1_1") (pintype "passive"))
      (node (ref "M2") (pin "1") (pinfunction "1_1") (pintype "passive"))
      (node (ref "M3") (pin "1") (pinfunction "1_1") (pintype "passive"))
      (node (ref "PI") (pin "14") (pinfunction "14_14") (pintype "passive"))
      (node (ref "PI") (pin "20") (pinfunction "20_20") (pintype "passive"))
      (node (ref "PI") (pin "25") (pinfunction "25_25") (pintype "passive"))
      (node (ref "PI") (pin "30") (pinfunction "30_30") (pintype "passive"))
      (node (ref "PI") (pin "34") (pinfunction "34_34") (pintype "passive"))
      (node (ref "PI") (pin "39") (pinfunction "39_39") (pintype "passive"))
      (node (ref "PI") (pin "6") (pinfunction "6_6") (pintype "passive"))
      (node (ref "PI") (pin "9") (pinfunction "9_9") (pintype "passive"))
      (node (ref "Q2") (pin "2") (pinfunction "E_2") (pintype "passive"))
      (node (ref "Q3") (pin "2") (pinfunction "E_2") (pintype "passive"))
      (node (ref "Q4") (pin "2") (pinfunction "E_2") (pintype "passive"))
      (node (ref "Q5") (pin "2") (pinfunction "E_2") (pintype "passive"))
      (node (ref "Q6") (pin "2") (pinfunction "E_2") (pintype "passive"))
      (node (ref "R13") (pin "1") (pintype "passive"))
      (node (ref "R4") (pin "2") (pintype "passive"))
      (node (ref "R8") (pin "2") (pintype "passive"))
      (node (ref "U1") (pin "1") (pinfunction "GND_1") (pintype "power_in"))
      (node (ref "U1") (pin "104") (pinfunction "GND_104") (pintype "power_in"))
      (node (ref "U1") (pin "108") (pinfunction "GND_108") (pintype "power_in"))
      (node (ref "U1") (pin "120") (pinfunction "GND_120") (pintype "power_in"))
      (node (ref "U1") (pin "121") (pinfunction "GND_121") (pintype "power_in"))
      (node (ref "U1") (pin "126") (pinfunction "GND_126") (pintype "power_in"))
      (node (ref "U1") (pin "127") (pinfunction "GND_127") (pintype "power_in"))
      (node (ref "U1") (pin "129") (pinfunction "GND_129") (pintype "power_in"))
      (node (ref "U1") (pin "133") (pinfunction "GND_133") (pintype "power_in"))
      (node (ref "U1") (pin "37") (pinfunction "GND_37") (pintype "power_in"))
      (node (ref "U1") (pin "44") (pinfunction "GND_44") (pintype "power_in"))
      (node (ref "U1") (pin "5") (pinfunction "GND_5") (pintype "power_in"))
      (node (ref "U1") (pin "50") (pinfunction "GND_50") (pintype "power_in"))
      (node (ref "U1") (pin "64") (pinfunction "GND_64") (pintype "power_in"))
      (node (ref "U1") (pin "9") (pinfunction "GND_9") (pintype "power_in"))
      (node (ref "U1") (pin "94") (pinfunction "GND_94") (pintype "power_in"))
      (node (ref "U10") (pin "10") (pinfunction "GND_10") (pintype "power_in"))
      (node (ref "U11") (pin "10") (pinfunction "GND_10") (pintype "power_in"))
      (node (ref "U12") (pin "1") (pinfunction "GND_1") (pintype "power_in"))
      (node (ref "U13") (pin "1") (pinfunction "GND_1") (pintype "power_in"))
      (node (ref "U2") (pin "12") (pinfunction "GND_12") (pintype "power_in"))
      (node (ref "U3") (pin "12") (pinfunction "GND_12") (pintype "power_in"))
      (node (ref "U4") (pin "12") (pinfunction "GND_12") (pintype "power_in"))
      (node (ref "U5") (pin "10") (pinfunction "1B5_10") (pintype "bidirectional"))
      (node (ref "U5") (pin "11") (pinfunction "1A5_11") (pintype "bidirectional"))
      (node (ref "U5") (pin "12") (pinfunction "GND_12") (pintype "power_in"))
      (node (ref "U5") (pin "6") (pinfunction "1B3_6") (pintype "bidirectional"))
      (node (ref "U5") (pin "7") (pinfunction "1A3_7") (pintype "bidirectional"))
      (node (ref "U5") (pin "8") (pinfunction "1A4_8") (pintype "bidirectional"))
      (node (ref "U5") (pin "9") (pinfunction "1B4_9") (pintype "bidirectional"))
      (node (ref "U6") (pin "12") (pinfunction "GND_12") (pintype "power_in"))
      (node (ref "U7") (pin "12") (pinfunction "GND_12") (pintype "power_in"))
      (node (ref "U8") (pin "10") (pinfunction "GND_10") (pintype "power_in"))
      (node (ref "U9") (pin "10") (pinfunction "GND_10") (pintype "power_in"))
    )
    (net (code "231") (name "Net-(LED_1.2-+)") (class "Default")
      (node (ref "LED_1.2") (pin "2") (pinfunction "+_2") (pintype "passive"))
      (node (ref "RN10") (pin "5") (pinfunction "5_5") (pintype "passive"))
    )
    (net (code "232") (name "Net-(LED_1.2--)") (class "Default")
      (node (ref "LED_1.2") (pin "1") (pinfunction "-_1") (pintype "passive"))
      (node (ref "Q3") (pin "3") (pinfunction "C_3") (pintype "passive"))
    )
    (net (code "233") (name "Net-(LED_3.3-+)") (class "Default")
      (node (ref "LED_3.3") (pin "2") (pinfunction "+_2") (pintype "passive"))
      (node (ref "RN10") (pin "6") (pinfunction "6_6") (pintype "passive"))
    )
    (net (code "234") (name "Net-(LED_3.3--)") (class "Default")
      (node (ref "LED_3.3") (pin "1") (pinfunction "-_1") (pintype "passive"))
      (node (ref "Q4") (pin "3") (pinfunction "C_3") (pintype "passive"))
    )
    (net (code "235") (name "Net-(LED_FPGA-+)") (class "Default")
      (node (ref "LED_FPGA") (pin "2") (pinfunction "+_2") (pintype "passive"))
      (node (ref "RN10") (pin "8") (pinfunction "8_8") (pintype "passive"))
    )
    (net (code "236") (name "Net-(LED_FPGA--)") (class "Default")
      (node (ref "LED_FPGA") (pin "1") (pinfunction "-_1") (pintype "passive"))
      (node (ref "Q6") (pin "3") (pinfunction "C_3") (pintype "passive"))
    )
    (net (code "237") (name "Net-(LED_PI-+)") (class "Default")
      (node (ref "LED_PI") (pin "2") (pinfunction "+_2") (pintype "passive"))
      (node (ref "RN10") (pin "7") (pinfunction "7_7") (pintype "passive"))
    )
    (net (code "238") (name "Net-(LED_PI--)") (class "Default")
      (node (ref "LED_PI") (pin "1") (pinfunction "-_1") (pintype "passive"))
      (node (ref "Q5") (pin "3") (pinfunction "C_3") (pintype "passive"))
    )
    (net (code "239") (name "Net-(Q1-D)") (class "Default")
      (node (ref "C19") (pin "1") (pinfunction "1_1") (pintype "passive"))
      (node (ref "C21") (pin "1") (pinfunction "1_1") (pintype "passive"))
      (node (ref "Q1") (pin "3") (pinfunction "D_3") (pintype "passive"))
      (node (ref "R1") (pin "1") (pintype "passive"))
      (node (ref "U12") (pin "3") (pinfunction "IN_3") (pintype "power_in"))
      (node (ref "U13") (pin "3") (pinfunction "IN_3") (pintype "power_in"))
    )
    (net (code "240") (name "Net-(Q1-G)") (class "Default")
      (node (ref "Q1") (pin "1") (pinfunction "G_1") (pintype "passive"))
      (node (ref "Q2") (pin "3") (pinfunction "C_3") (pintype "passive"))
      (node (ref "R2") (pin "1") (pintype "passive"))
    )
    (net (code "241") (name "Net-(Q2-B)") (class "Default")
      (node (ref "Q2") (pin "1") (pinfunction "B_1") (pintype "passive"))
      (node (ref "R19") (pin "1") (pintype "passive"))
    )
    (net (code "242") (name "Net-(Q3-B)") (class "Default")
      (node (ref "Q3") (pin "1") (pinfunction "B_1") (pintype "passive"))
      (node (ref "R5") (pin "1") (pintype "passive"))
    )
    (net (code "243") (name "Net-(Q4-B)") (class "Default")
      (node (ref "Q4") (pin "1") (pinfunction "B_1") (pintype "passive"))
      (node (ref "R6") (pin "1") (pintype "passive"))
    )
    (net (code "244") (name "Net-(Q5-B)") (class "Default")
      (node (ref "Q5") (pin "1") (pinfunction "B_1") (pintype "passive"))
      (node (ref "R9") (pin "1") (pintype "passive"))
    )
    (net (code "245") (name "Net-(Q6-B)") (class "Default")
      (node (ref "Q6") (pin "1") (pinfunction "B_1") (pintype "passive"))
      (node (ref "R10") (pin "1") (pintype "passive"))
    )
    (net (code "246") (name "VCC") (class "Default")
      (node (ref "C1") (pin "2") (pinfunction "2_2") (pintype "passive"))
      (node (ref "C10") (pin "2") (pinfunction "2_2") (pintype "passive"))
      (node (ref "C12") (pin "2") (pinfunction "2_2") (pintype "passive"))
      (node (ref "C2") (pin "2") (pinfunction "2_2") (pintype "passive"))
      (node (ref "C20") (pin "1") (pinfunction "1_1") (pintype "passive"))
      (node (ref "C3") (pin "2") (pinfunction "2_2") (pintype "passive"))
      (node (ref "C4") (pin "2") (pinfunction "2_2") (pintype "passive"))
      (node (ref "C5") (pin "2") (pinfunction "2_2") (pintype "passive"))
      (node (ref "C6") (pin "2") (pinfunction "2_2") (pintype "passive"))
      (node (ref "EXT") (pin "10") (pinfunction "10_10") (pintype "passive"))
      (node (ref "JTAG") (pin "1") (pinfunction "1_1") (pintype "passive"))
      (node (ref "R16") (pin "1") (pinfunction "1_1") (pintype "passive"))
      (node (ref "R17") (pin "1") (pinfunction "1_1") (pintype "passive"))
      (node (ref "R18") (pin "2") (pinfunction "2_2") (pintype "passive"))
      (node (ref "R3") (pin "2") (pintype "passive"))
      (node (ref "R6") (pin "2") (pintype "passive"))
      (node (ref "R7") (pin "2") (pintype "passive"))
      (node (ref "RN9") (pin "1") (pinfunction "1_1") (pintype "passive"))
      (node (ref "RN9") (pin "2") (pinfunction "2_2") (pintype "passive"))
      (node (ref "RN9") (pin "3") (pinfunction "3_3") (pintype "passive"))
      (node (ref "RN9") (pin "4") (pinfunction "4_4") (pintype "passive"))
      (node (ref "U1") (pin "12") (pinfunction "VCCIO1C_1D_12") (pintype "power_in"))
      (node (ref "U1") (pin "122") (pinfunction "VCCIO3A_122") (pintype "power_in"))
      (node (ref "U1") (pin "143") (pinfunction "VCCIO1E_143") (pintype "power_in"))
      (node (ref "U1") (pin "21") (pinfunction "VCCIO1B_21") (pintype "power_in"))
      (node (ref "U1") (pin "23") (pinfunction "VCCIO1A_23") (pintype "power_in"))
      (node (ref "U1") (pin "51") (pinfunction "VCCIO4B_51") (pintype "power_in"))
      (node (ref "U1") (pin "52") (pinfunction "VCCIO4B_52") (pintype "power_in"))
      (node (ref "U1") (pin "62") (pinfunction "VCCIO4A_62") (pintype "power_in"))
      (node (ref "U1") (pin "63") (pinfunction "VCCIO4A_63") (pintype "power_in"))
      (node (ref "U1") (pin "88") (pinfunction "VCCIO3E_88") (pintype "power_in"))
      (node (ref "U1") (pin "91") (pinfunction "VCCIO3D_91") (pintype "power_in"))
      (node (ref "U1") (pin "95") (pinfunction "VCCIO3B_3C_95") (pintype "power_in"))
      (node (ref "U10") (pin "20") (pinfunction "VCC_20") (pintype "power_in"))
      (node (ref "U11") (pin "20") (pinfunction "VCC_20") (pintype "power_in"))
      (node (ref "U12") (pin "2") (pinfunction "OUT_2") (pintype "power_in"))
      (node (ref "U12") (pin "4") (pinfunction "TAB_4") (pintype "power_in"))
      (node (ref "U8") (pin "20") (pinfunction "VCC_20") (pintype "power_in"))
      (node (ref "U9") (pin "20") (pinfunction "VCC_20") (pintype "power_in"))
    )
    (net (code "247") (name "VCC_1.2") (class "Default")
      (node (ref "C13") (pin "2") (pinfunction "2_2") (pintype "passive"))
      (node (ref "C14") (pin "2") (pinfunction "2_2") (pintype "passive"))
      (node (ref "C15") (pin "2") (pinfunction "2_2") (pintype "passive"))
      (node (ref "C16") (pin "2") (pinfunction "2_2") (pintype "passive"))
      (node (ref "C22") (pin "1") (pinfunction "1_1") (pintype "passive"))
      (node (ref "C24") (pin "2") (pinfunction "2_2") (pintype "passive"))
      (node (ref "R5") (pin "2") (pintype "passive"))
      (node (ref "U1") (pin "107") (pinfunction "AVCC_TR_107") (pintype "power_in"))
      (node (ref "U1") (pin "125") (pinfunction "VCC_125") (pintype "power_in"))
      (node (ref "U1") (pin "128") (pinfunction "VCC_128") (pintype "power_in"))
      (node (ref "U1") (pin "13") (pinfunction "VCC_13") (pintype "power_in"))
      (node (ref "U1") (pin "130") (pinfunction "VCC_130") (pintype "power_in"))
      (node (ref "U1") (pin "2") (pinfunction "AVCC_TL_2") (pintype "power_in"))
      (node (ref "U1") (pin "22") (pinfunction "VCC_22") (pintype "power_in"))
      (node (ref "U1") (pin "49") (pinfunction "VCC_49") (pintype "power_in"))
      (node (ref "U1") (pin "57") (pinfunction "VCC_57") (pintype "power_in"))
      (node (ref "U1") (pin "73") (pinfunction "AVCC_BR_73") (pintype "power_in"))
      (node (ref "U1") (pin "85") (pinfunction "VCC_85") (pintype "power_in"))
      (node (ref "U1") (pin "96") (pinfunction "VCC_96") (pintype "power_in"))
      (node (ref "U13") (pin "2") (pinfunction "OUT_2") (pintype "power_in"))
      (node (ref "U13") (pin "4") (pinfunction "TAB_4") (pintype "power_in"))
    )
    (net (code "248") (name "VCC_3.3") (class "Default")
      (node (ref "PI") (pin "17") (pinfunction "17_17") (pintype "passive"))
      (node (ref "R19") (pin "2") (pintype "passive"))
      (node (ref "R9") (pin "2") (pintype "passive"))
    )
    (net (code "249") (name "unconnected-(CN1--12V_P150-PadP$150)") (class "Default")
      (node (ref "CN1") (pin "P$150") (pinfunction "-12V_P150_P$150") (pintype "passive"))
    )
    (net (code "250") (name "unconnected-(CN1-LEFT_P147-PadP$147)") (class "Default")
      (node (ref "CN1") (pin "P$147") (pinfunction "LEFT_P147_P$147") (pintype "passive"))
    )
    (net (code "251") (name "unconnected-(CN1-RIGHT_P148-PadP$148)") (class "Default")
      (node (ref "CN1") (pin "P$148") (pinfunction "RIGHT_P148_P$148") (pintype "passive"))
    )
    (net (code "252") (name "unconnected-(PI-Pad1)") (class "Default")
      (node (ref "PI") (pin "1") (pinfunction "1_1") (pintype "passive"))
    )
    (net (code "253") (name "unconnected-(U1N-REF_RES-Pad36)") (class "Default")
      (node (ref "U1") (pin "36") (pinfunction "REF_RES_36") (pintype "passive+no_connect"))
    )
  )
)
